# SpeedOfLightController.net
KiCad netlist of a schematic drawn in EAGLE
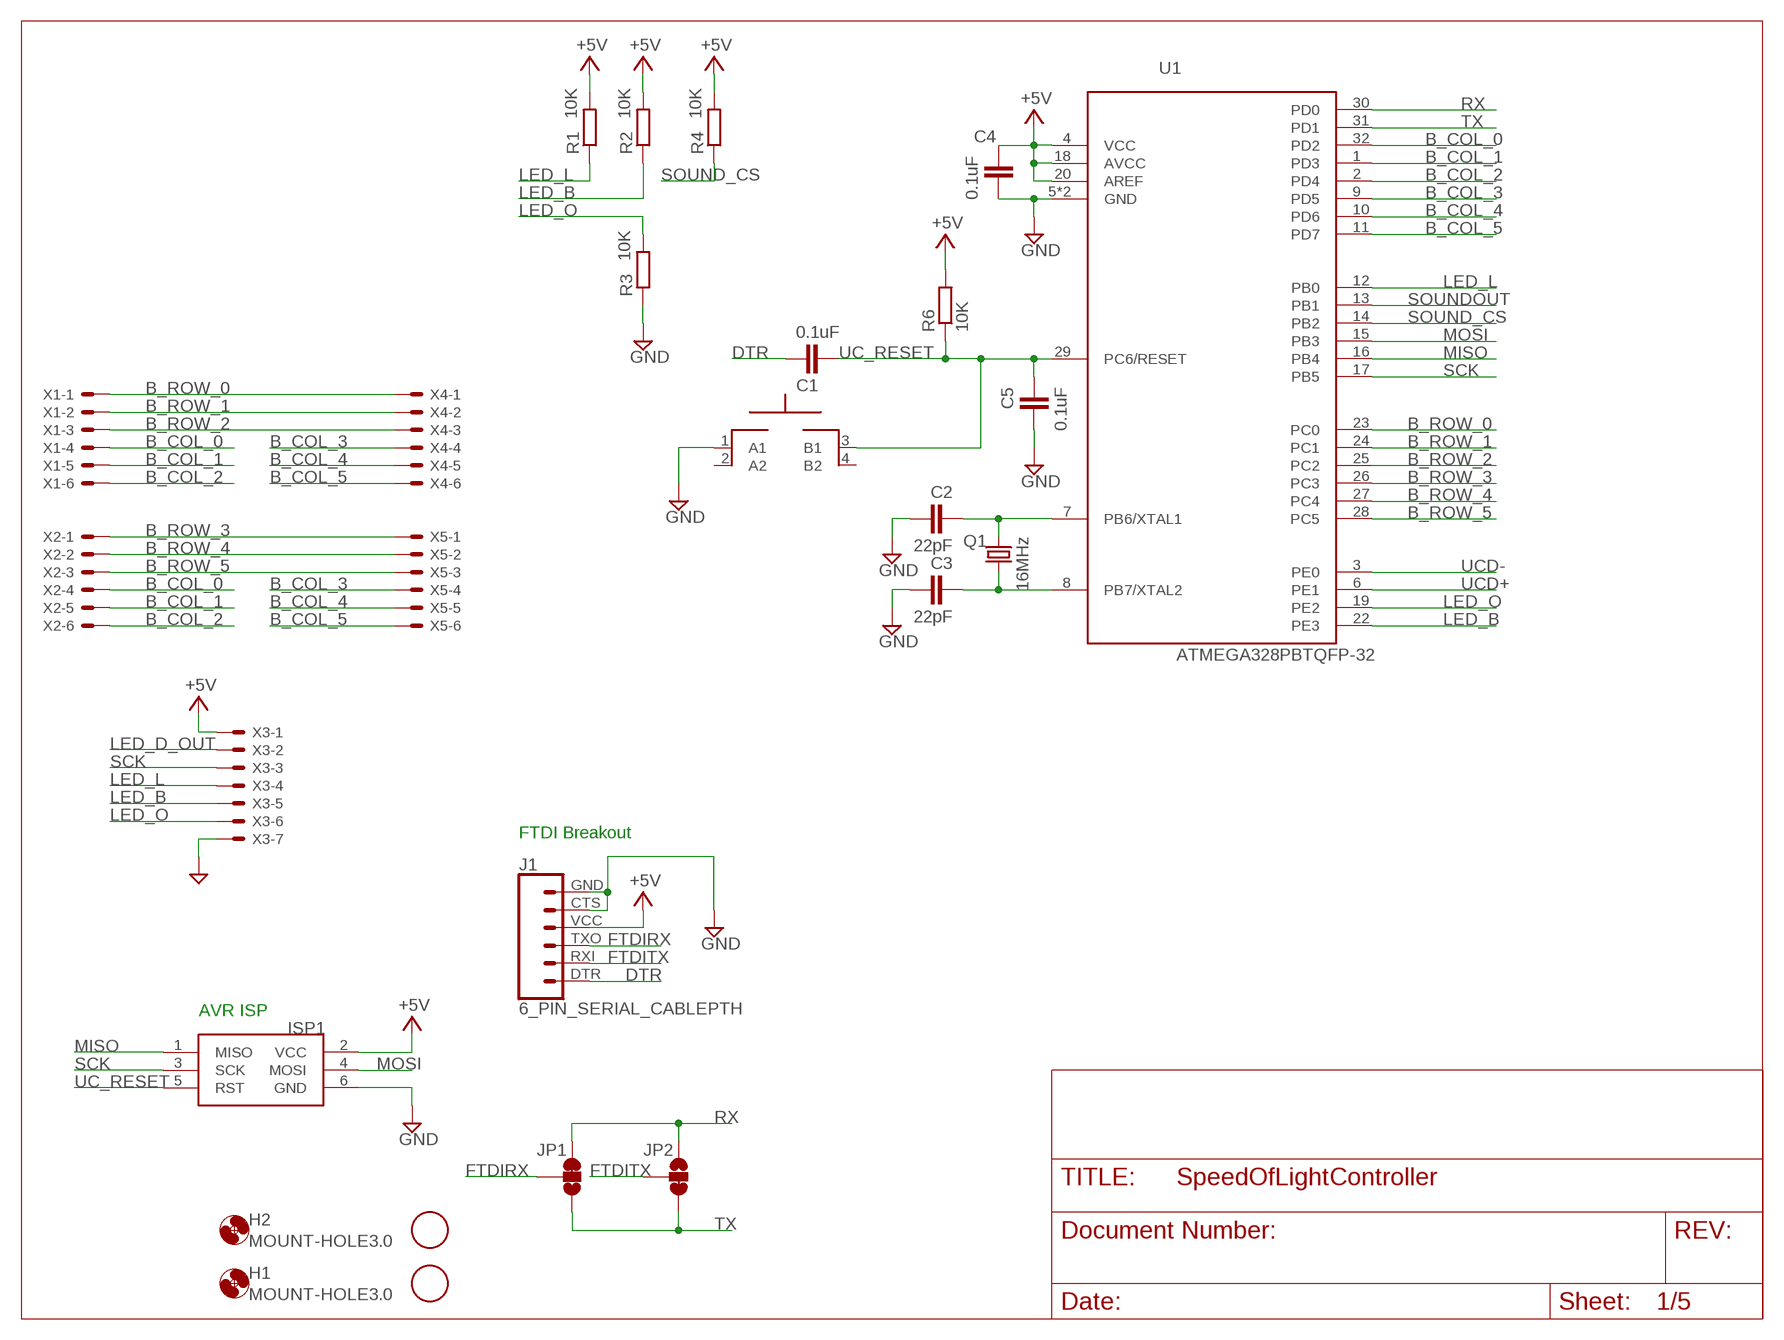
[diagram p0: schematic, sheet 1]
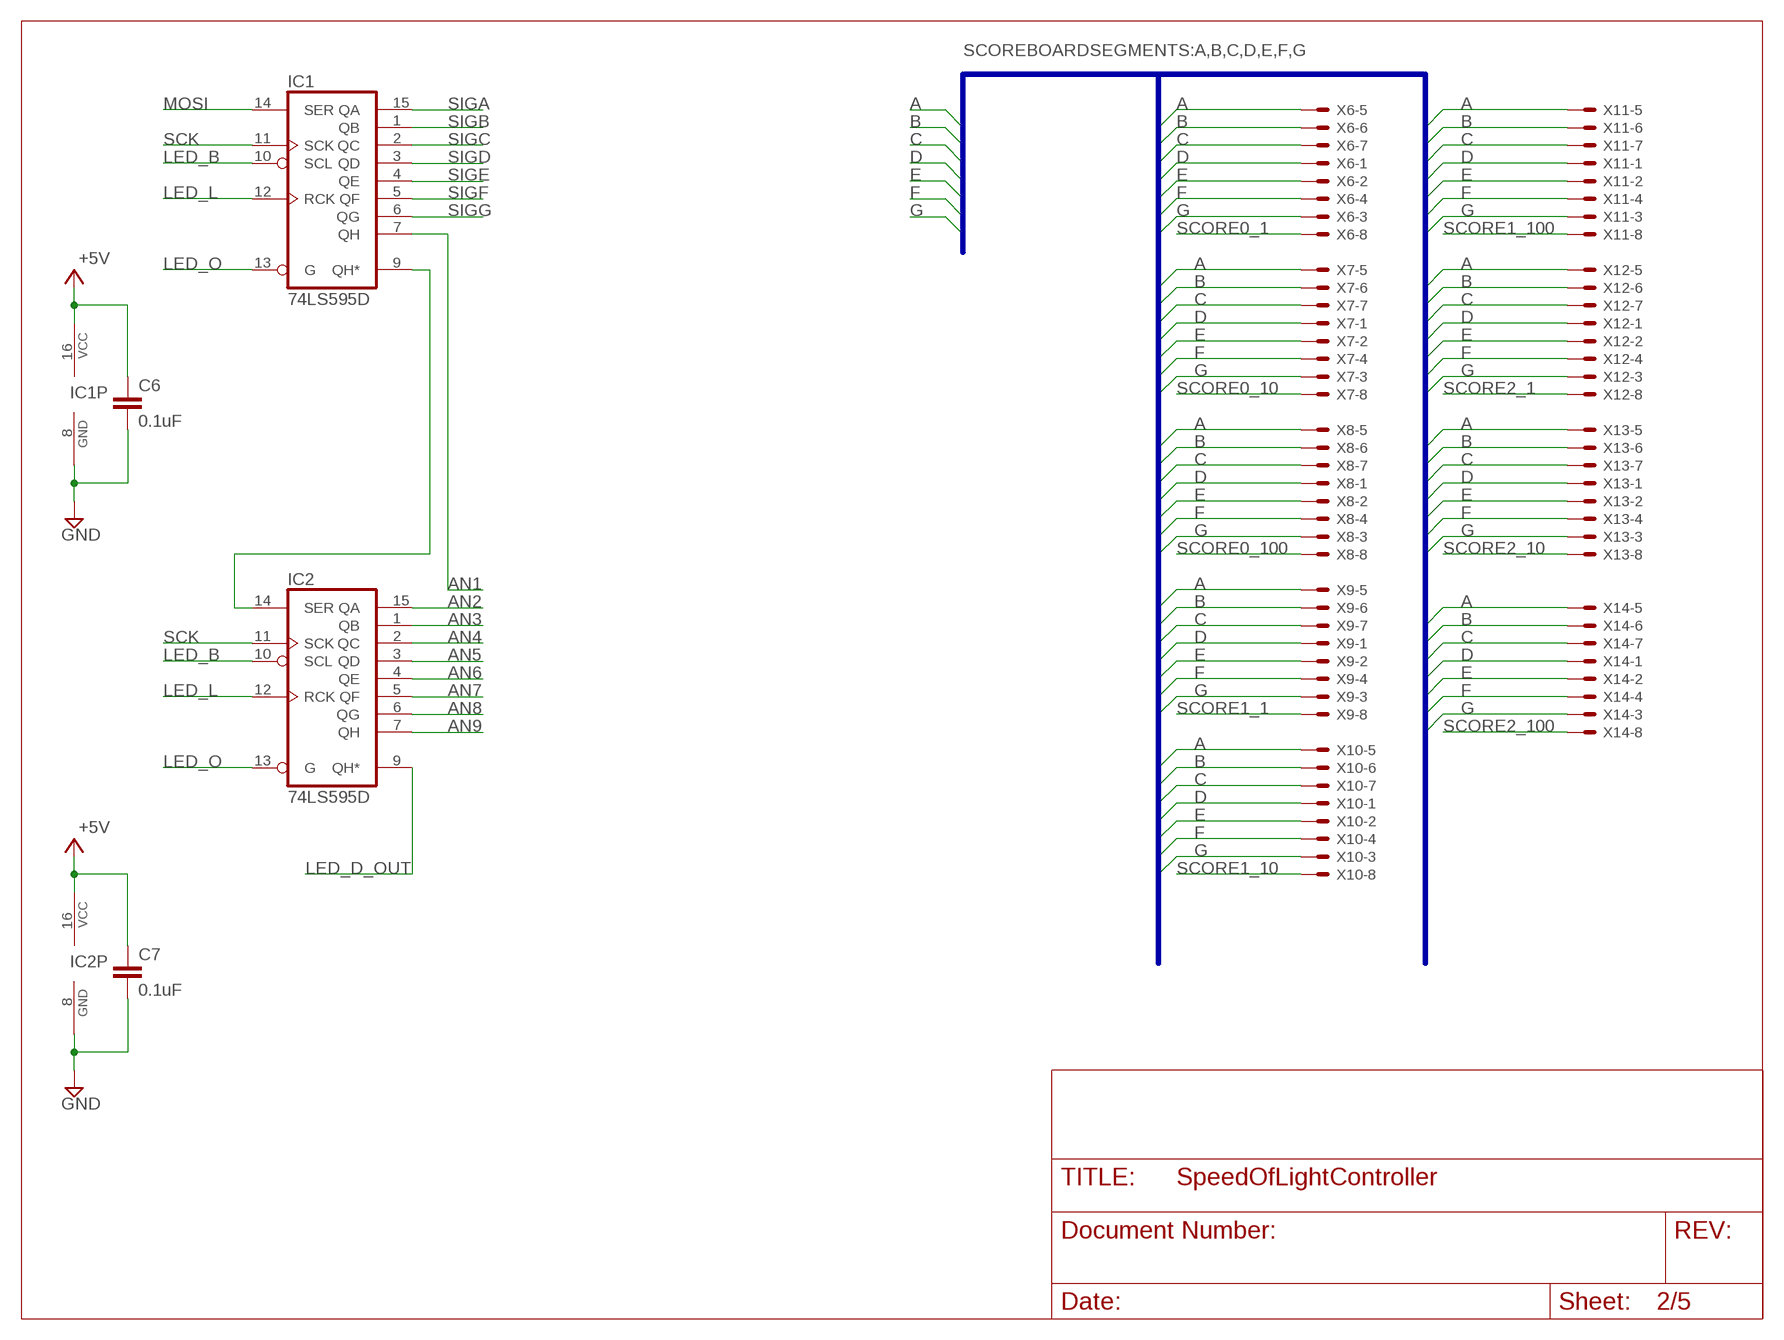
[diagram p1: schematic, sheet 2]
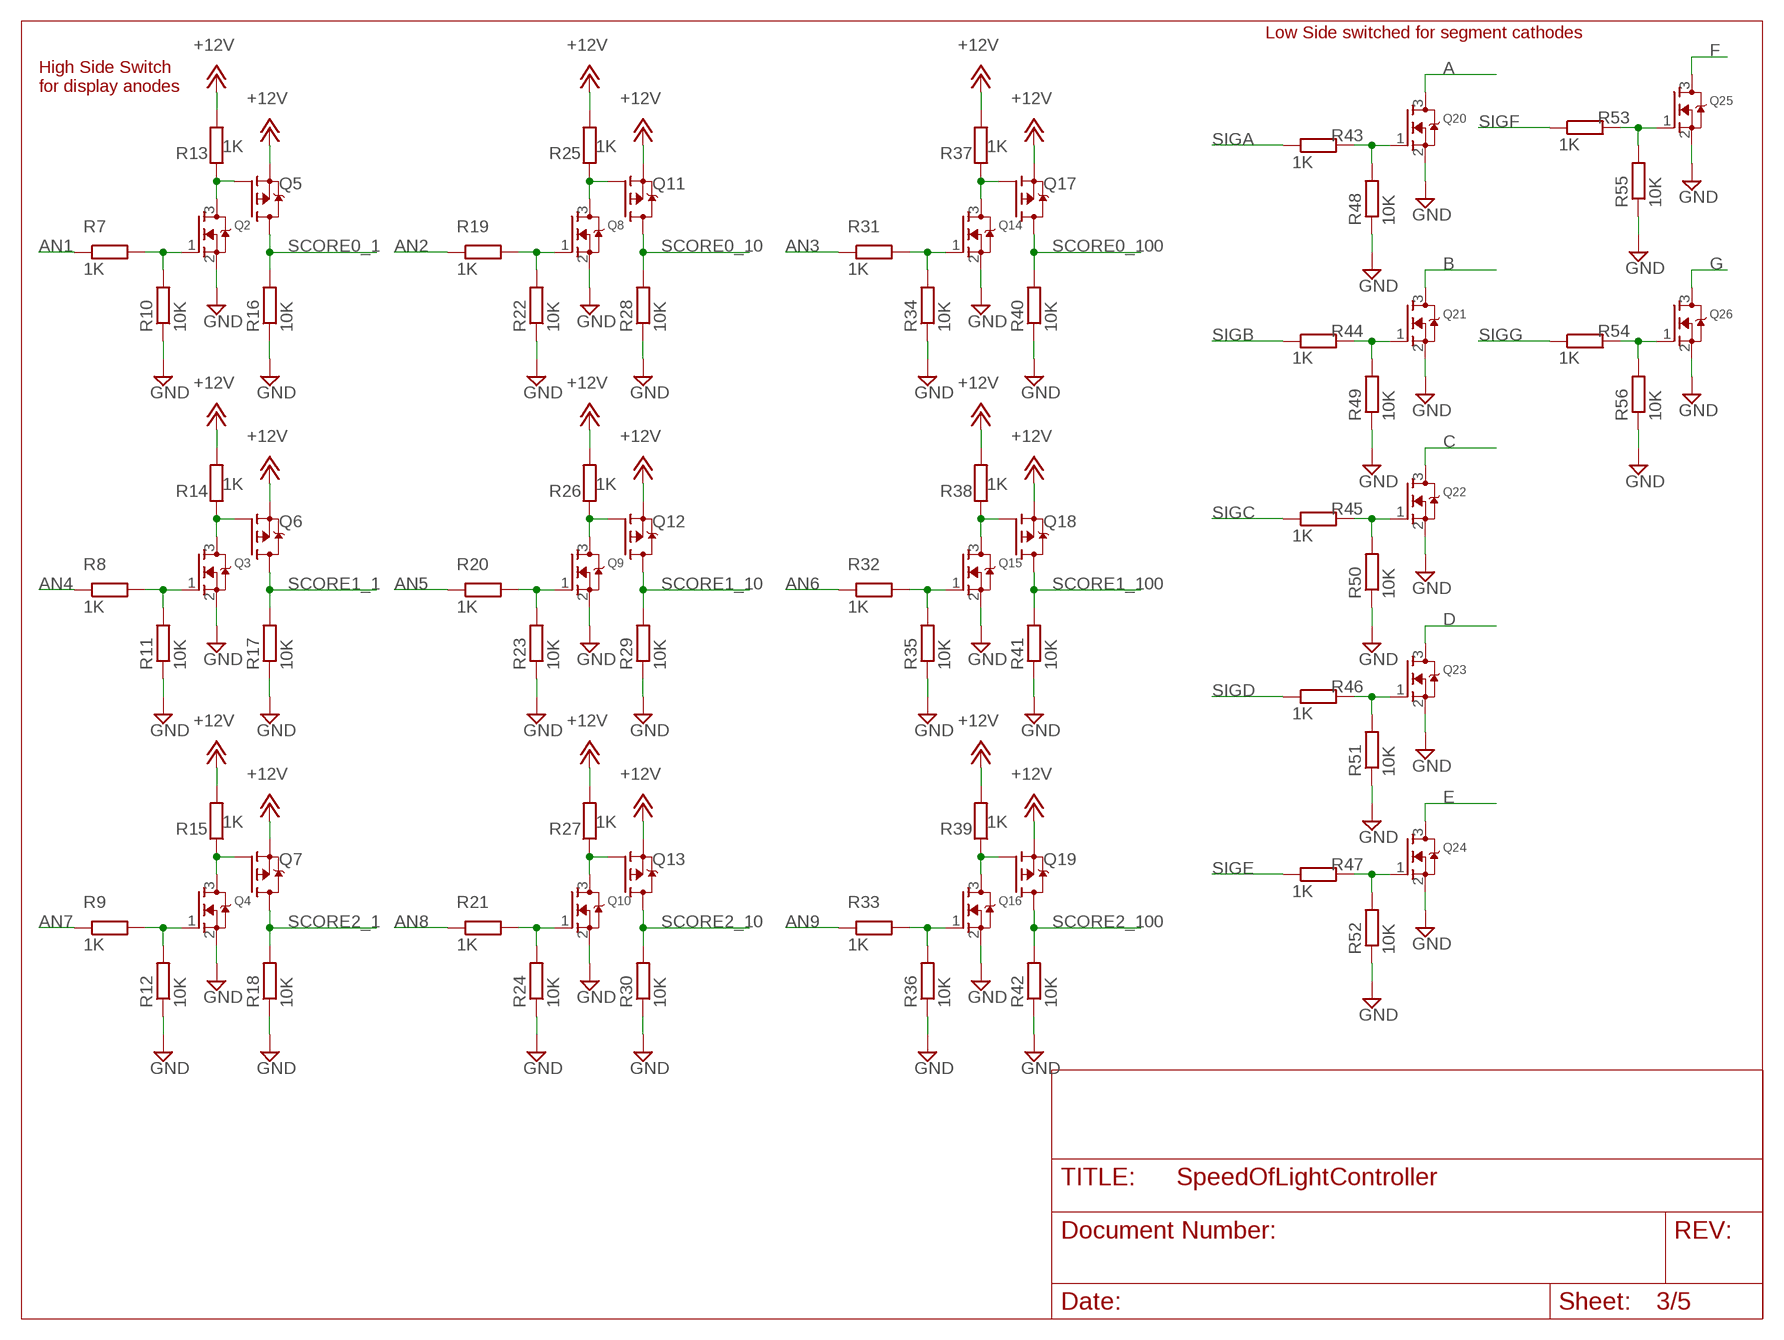
[diagram p2: schematic, sheet 3]
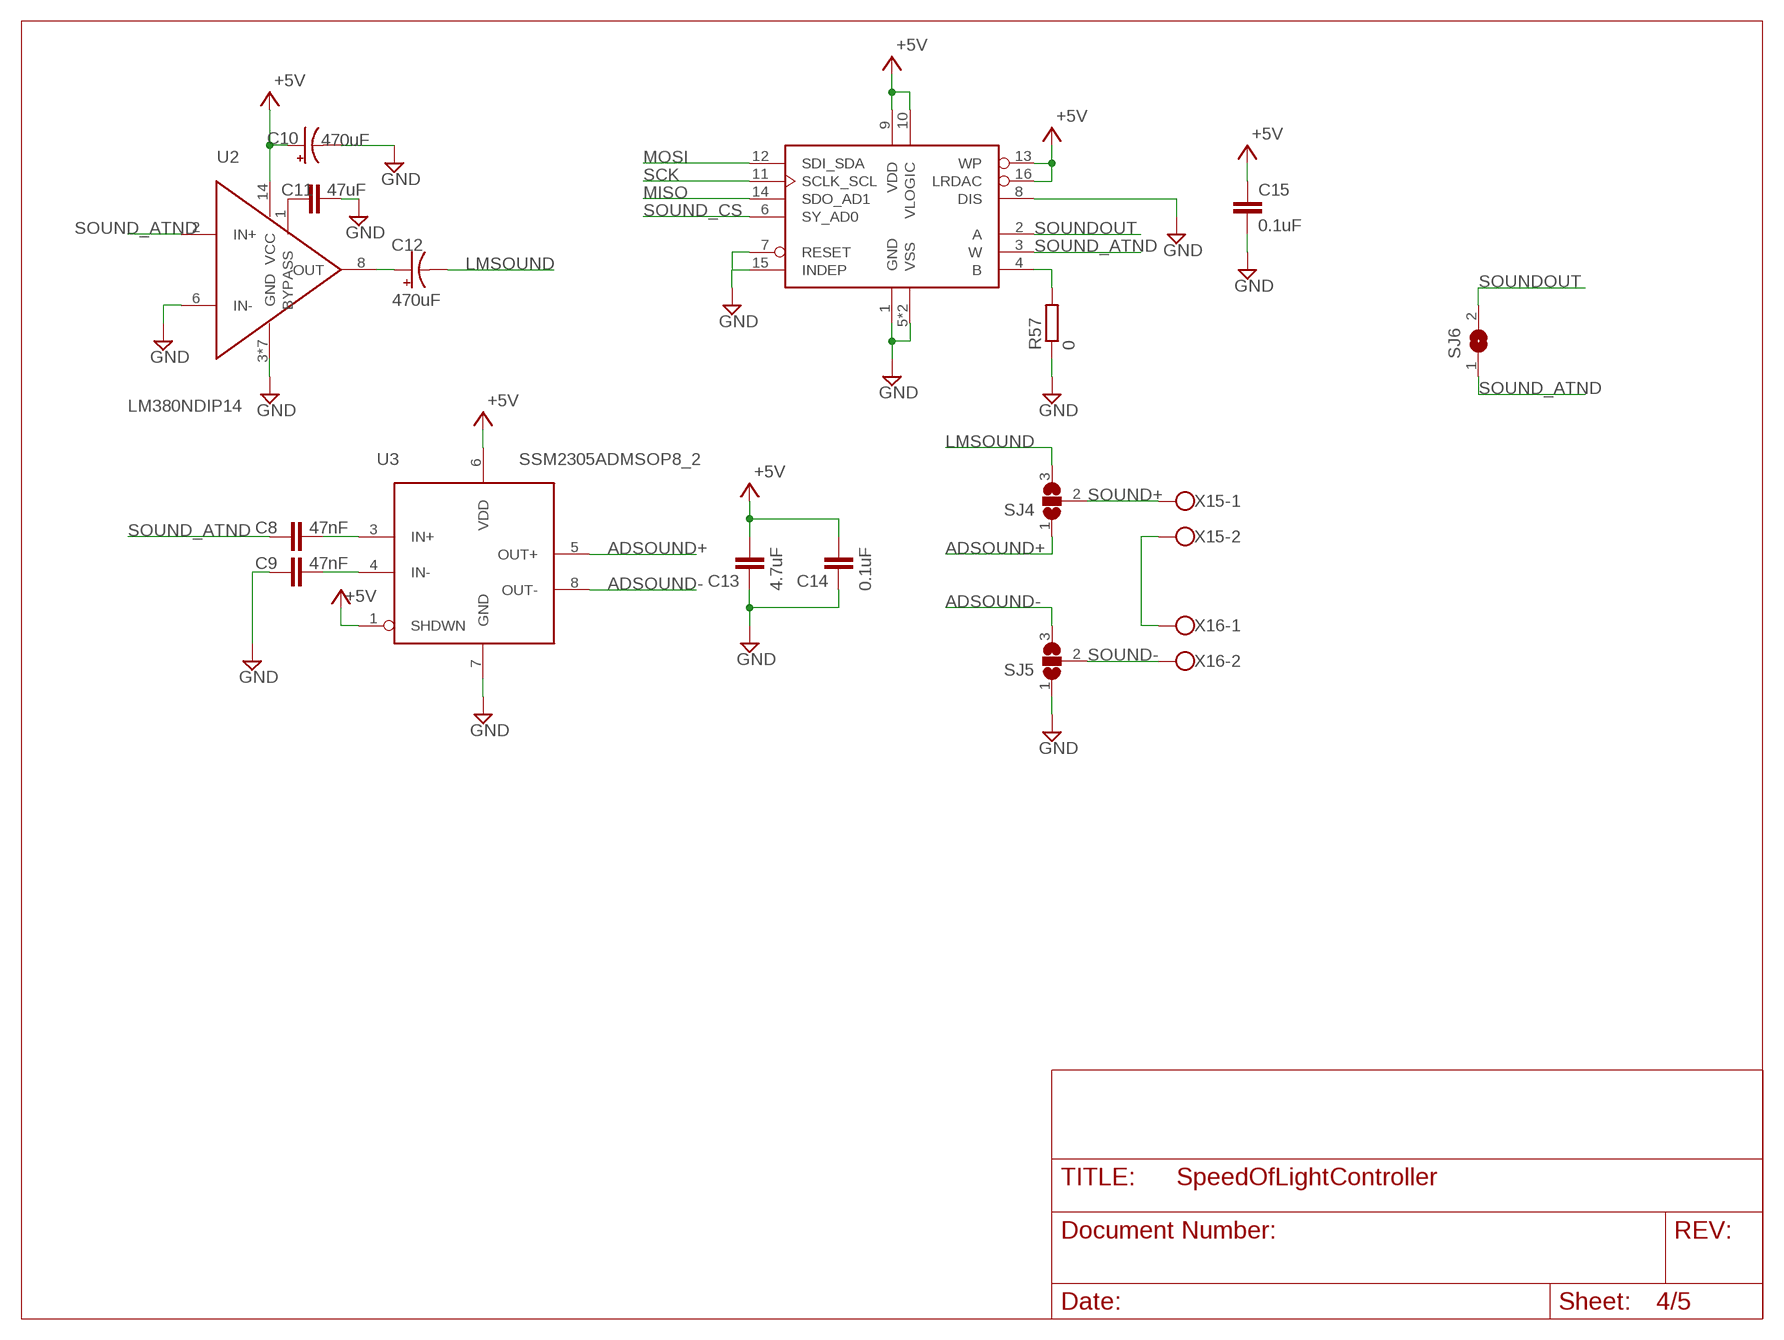
[diagram p3: schematic, sheet 4]
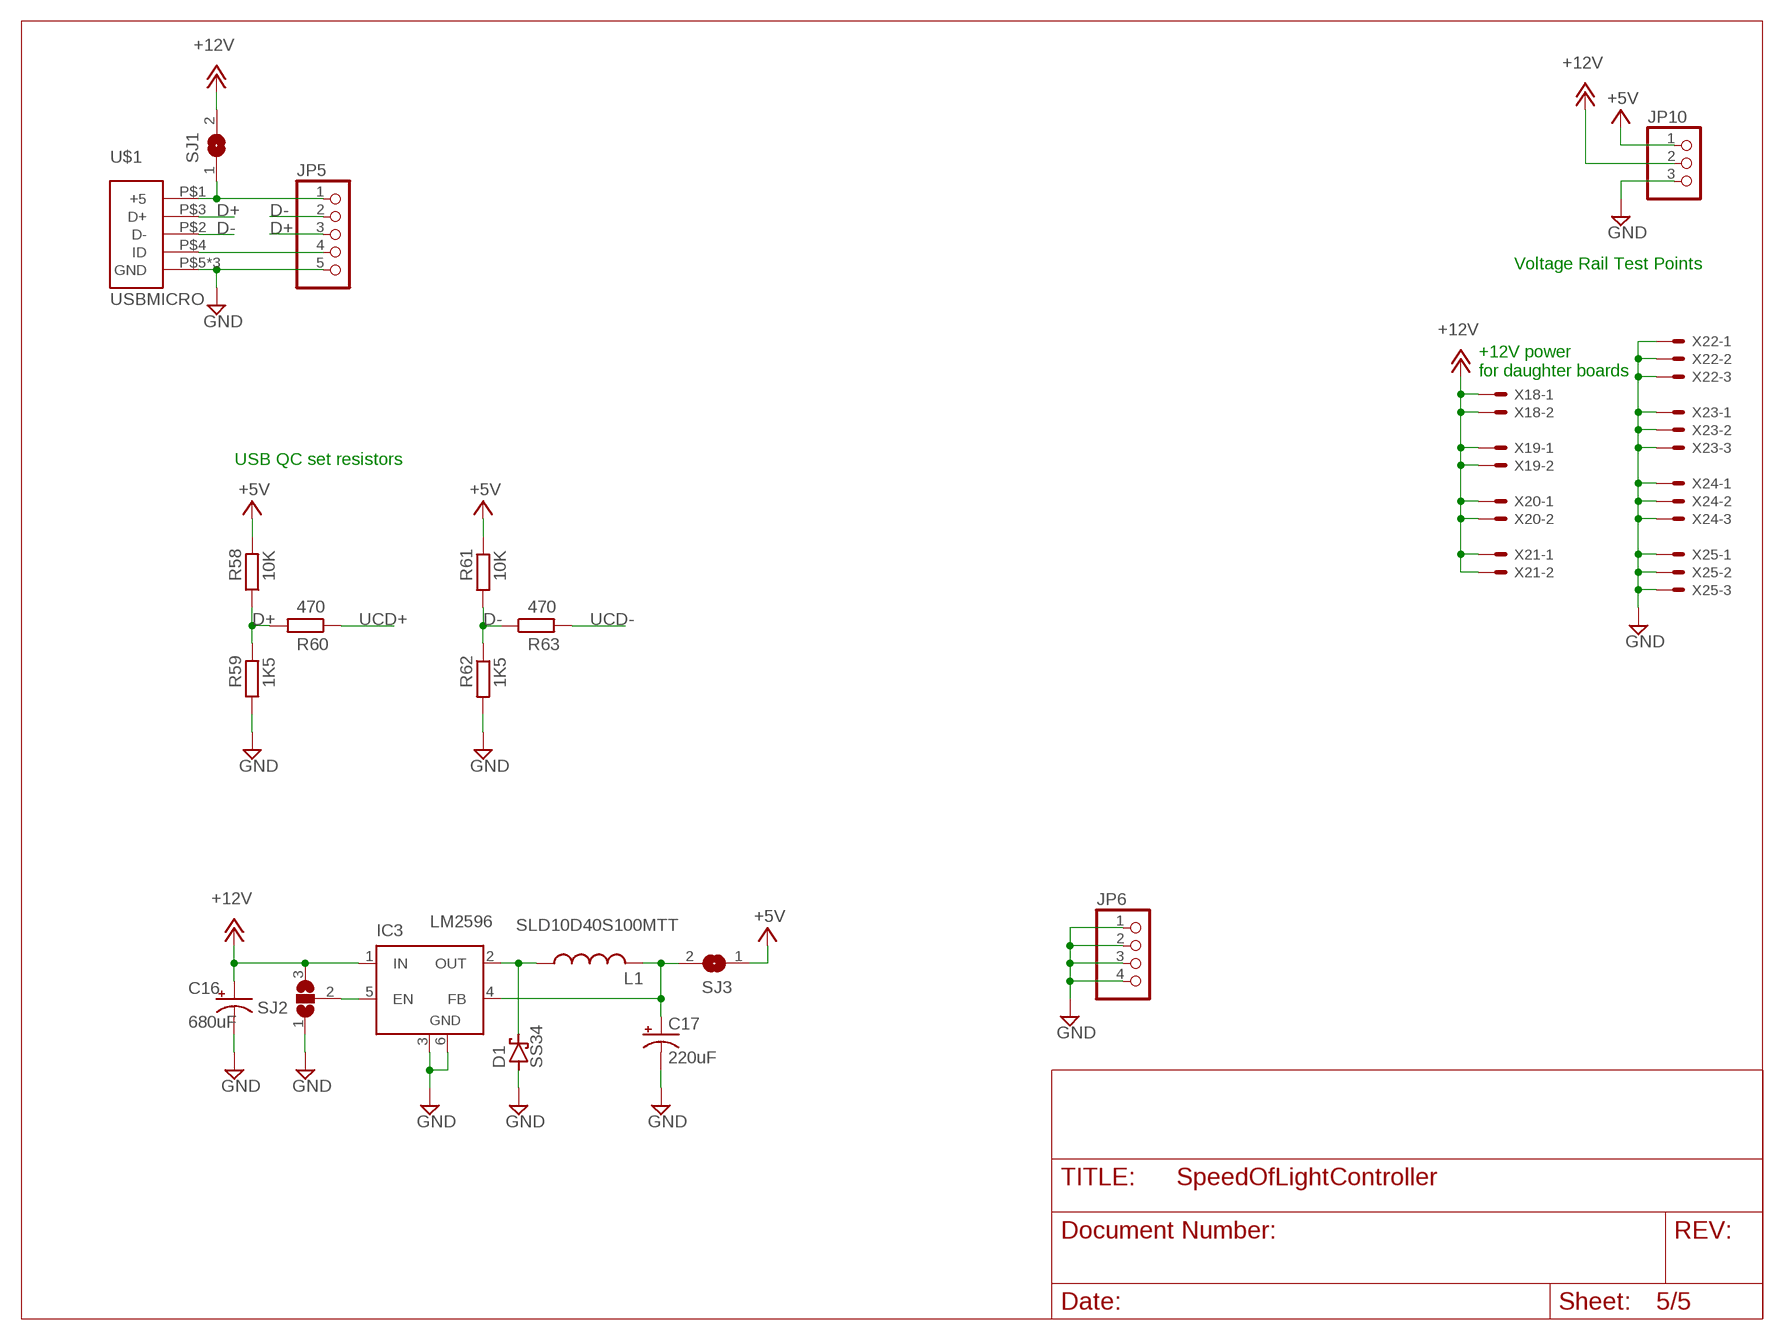
[diagram p4: schematic, sheet 5]

(export (version "E")
  (design (tool "Eeschema 10.0.6"))
  (components
    (comp (ref "Q2")
      (value "AO3414SOT23")
      (footprint "eagle-import:SOT95P240X110-3N")
      (libsource (lib "eagle-import") (part "AO3414SOT23"))
    )
    (comp (ref "Q3")
      (value "AO3414SOT23")
      (footprint "eagle-import:SOT95P240X110-3N")
      (libsource (lib "eagle-import") (part "AO3414SOT23"))
    )
    (comp (ref "Q4")
      (value "AO3414SOT23")
      (footprint "eagle-import:SOT95P240X110-3N")
      (libsource (lib "eagle-import") (part "AO3414SOT23"))
    )
    (comp (ref "Q5")
      (value "AO3415")
      (footprint "eagle-import:SOT95P240X110-3N")
      (libsource (lib "eagle-import") (part "AO3415"))
    )
    (comp (ref "Q6")
      (value "AO3415")
      (footprint "eagle-import:SOT95P240X110-3N")
      (libsource (lib "eagle-import") (part "AO3415"))
    )
    (comp (ref "Q7")
      (value "AO3415")
      (footprint "eagle-import:SOT95P240X110-3N")
      (libsource (lib "eagle-import") (part "AO3415"))
    )
    (comp (ref "Q8")
      (value "AO3414SOT23")
      (footprint "eagle-import:SOT95P240X110-3N")
      (libsource (lib "eagle-import") (part "AO3414SOT23"))
    )
    (comp (ref "Q9")
      (value "AO3414SOT23")
      (footprint "eagle-import:SOT95P240X110-3N")
      (libsource (lib "eagle-import") (part "AO3414SOT23"))
    )
    (comp (ref "Q10")
      (value "AO3414SOT23")
      (footprint "eagle-import:SOT95P240X110-3N")
      (libsource (lib "eagle-import") (part "AO3414SOT23"))
    )
    (comp (ref "Q11")
      (value "AO3415")
      (footprint "eagle-import:SOT95P240X110-3N")
      (libsource (lib "eagle-import") (part "AO3415"))
    )
    (comp (ref "Q12")
      (value "AO3415")
      (footprint "eagle-import:SOT95P240X110-3N")
      (libsource (lib "eagle-import") (part "AO3415"))
    )
    (comp (ref "Q13")
      (value "AO3415")
      (footprint "eagle-import:SOT95P240X110-3N")
      (libsource (lib "eagle-import") (part "AO3415"))
    )
    (comp (ref "Q14")
      (value "AO3414SOT23")
      (footprint "eagle-import:SOT95P240X110-3N")
      (libsource (lib "eagle-import") (part "AO3414SOT23"))
    )
    (comp (ref "Q15")
      (value "AO3414SOT23")
      (footprint "eagle-import:SOT95P240X110-3N")
      (libsource (lib "eagle-import") (part "AO3414SOT23"))
    )
    (comp (ref "Q16")
      (value "AO3414SOT23")
      (footprint "eagle-import:SOT95P240X110-3N")
      (libsource (lib "eagle-import") (part "AO3414SOT23"))
    )
    (comp (ref "Q17")
      (value "AO3415")
      (footprint "eagle-import:SOT95P240X110-3N")
      (libsource (lib "eagle-import") (part "AO3415"))
    )
    (comp (ref "Q18")
      (value "AO3415")
      (footprint "eagle-import:SOT95P240X110-3N")
      (libsource (lib "eagle-import") (part "AO3415"))
    )
    (comp (ref "Q19")
      (value "AO3415")
      (footprint "eagle-import:SOT95P240X110-3N")
      (libsource (lib "eagle-import") (part "AO3415"))
    )
    (comp (ref "Q20")
      (value "AO3414SOT23")
      (footprint "eagle-import:SOT95P240X110-3N")
      (libsource (lib "eagle-import") (part "AO3414SOT23"))
    )
    (comp (ref "Q21")
      (value "AO3414SOT23")
      (footprint "eagle-import:SOT95P240X110-3N")
      (libsource (lib "eagle-import") (part "AO3414SOT23"))
    )
    (comp (ref "Q22")
      (value "AO3414SOT23")
      (footprint "eagle-import:SOT95P240X110-3N")
      (libsource (lib "eagle-import") (part "AO3414SOT23"))
    )
    (comp (ref "Q23")
      (value "AO3414SOT23")
      (footprint "eagle-import:SOT95P240X110-3N")
      (libsource (lib "eagle-import") (part "AO3414SOT23"))
    )
    (comp (ref "Q24")
      (value "AO3414SOT23")
      (footprint "eagle-import:SOT95P240X110-3N")
      (libsource (lib "eagle-import") (part "AO3414SOT23"))
    )
    (comp (ref "Q25")
      (value "AO3414SOT23")
      (footprint "eagle-import:SOT95P240X110-3N")
      (libsource (lib "eagle-import") (part "AO3414SOT23"))
    )
    (comp (ref "Q26")
      (value "AO3414SOT23")
      (footprint "eagle-import:SOT95P240X110-3N")
      (libsource (lib "eagle-import") (part "AO3414SOT23"))
    )
    (comp (ref "R7")
      (value "1K")
      (footprint "eagle-import:R0805")
      (libsource (lib "eagle-import") (part "R-EU_R0805"))
    )
    (comp (ref "R8")
      (value "1K")
      (footprint "eagle-import:R0805")
      (libsource (lib "eagle-import") (part "R-EU_R0805"))
    )
    (comp (ref "R9")
      (value "1K")
      (footprint "eagle-import:R0805")
      (libsource (lib "eagle-import") (part "R-EU_R0805"))
    )
    (comp (ref "R10")
      (value "10K")
      (footprint "eagle-import:R0805")
      (libsource (lib "eagle-import") (part "R-EU_R0805"))
    )
    (comp (ref "R11")
      (value "10K")
      (footprint "eagle-import:R0805")
      (libsource (lib "eagle-import") (part "R-EU_R0805"))
    )
    (comp (ref "R12")
      (value "10K")
      (footprint "eagle-import:R0805")
      (libsource (lib "eagle-import") (part "R-EU_R0805"))
    )
    (comp (ref "R13")
      (value "1K")
      (footprint "eagle-import:R0805")
      (libsource (lib "eagle-import") (part "R-EU_R0805"))
    )
    (comp (ref "R14")
      (value "1K")
      (footprint "eagle-import:R0805")
      (libsource (lib "eagle-import") (part "R-EU_R0805"))
    )
    (comp (ref "R15")
      (value "1K")
      (footprint "eagle-import:R0805")
      (libsource (lib "eagle-import") (part "R-EU_R0805"))
    )
    (comp (ref "R16")
      (value "10K")
      (footprint "eagle-import:R0805")
      (libsource (lib "eagle-import") (part "R-EU_R0805"))
    )
    (comp (ref "R17")
      (value "10K")
      (footprint "eagle-import:R0805")
      (libsource (lib "eagle-import") (part "R-EU_R0805"))
    )
    (comp (ref "R18")
      (value "10K")
      (footprint "eagle-import:R0805")
      (libsource (lib "eagle-import") (part "R-EU_R0805"))
    )
    (comp (ref "R19")
      (value "1K")
      (footprint "eagle-import:R0805")
      (libsource (lib "eagle-import") (part "R-EU_R0805"))
    )
    (comp (ref "R20")
      (value "1K")
      (footprint "eagle-import:R0805")
      (libsource (lib "eagle-import") (part "R-EU_R0805"))
    )
    (comp (ref "R21")
      (value "1K")
      (footprint "eagle-import:R0805")
      (libsource (lib "eagle-import") (part "R-EU_R0805"))
    )
    (comp (ref "R22")
      (value "10K")
      (footprint "eagle-import:R0805")
      (libsource (lib "eagle-import") (part "R-EU_R0805"))
    )
    (comp (ref "R23")
      (value "10K")
      (footprint "eagle-import:R0805")
      (libsource (lib "eagle-import") (part "R-EU_R0805"))
    )
    (comp (ref "R24")
      (value "10K")
      (footprint "eagle-import:R0805")
      (libsource (lib "eagle-import") (part "R-EU_R0805"))
    )
    (comp (ref "R25")
      (value "1K")
      (footprint "eagle-import:R0805")
      (libsource (lib "eagle-import") (part "R-EU_R0805"))
    )
    (comp (ref "R26")
      (value "1K")
      (footprint "eagle-import:R0805")
      (libsource (lib "eagle-import") (part "R-EU_R0805"))
    )
    (comp (ref "R27")
      (value "1K")
      (footprint "eagle-import:R0805")
      (libsource (lib "eagle-import") (part "R-EU_R0805"))
    )
    (comp (ref "R28")
      (value "10K")
      (footprint "eagle-import:R0805")
      (libsource (lib "eagle-import") (part "R-EU_R0805"))
    )
    (comp (ref "R29")
      (value "10K")
      (footprint "eagle-import:R0805")
      (libsource (lib "eagle-import") (part "R-EU_R0805"))
    )
    (comp (ref "R30")
      (value "10K")
      (footprint "eagle-import:R0805")
      (libsource (lib "eagle-import") (part "R-EU_R0805"))
    )
    (comp (ref "R31")
      (value "1K")
      (footprint "eagle-import:R0805")
      (libsource (lib "eagle-import") (part "R-EU_R0805"))
    )
    (comp (ref "R32")
      (value "1K")
      (footprint "eagle-import:R0805")
      (libsource (lib "eagle-import") (part "R-EU_R0805"))
    )
    (comp (ref "R33")
      (value "1K")
      (footprint "eagle-import:R0805")
      (libsource (lib "eagle-import") (part "R-EU_R0805"))
    )
    (comp (ref "R34")
      (value "10K")
      (footprint "eagle-import:R0805")
      (libsource (lib "eagle-import") (part "R-EU_R0805"))
    )
    (comp (ref "R35")
      (value "10K")
      (footprint "eagle-import:R0805")
      (libsource (lib "eagle-import") (part "R-EU_R0805"))
    )
    (comp (ref "R36")
      (value "10K")
      (footprint "eagle-import:R0805")
      (libsource (lib "eagle-import") (part "R-EU_R0805"))
    )
    (comp (ref "R37")
      (value "1K")
      (footprint "eagle-import:R0805")
      (libsource (lib "eagle-import") (part "R-EU_R0805"))
    )
    (comp (ref "R38")
      (value "1K")
      (footprint "eagle-import:R0805")
      (libsource (lib "eagle-import") (part "R-EU_R0805"))
    )
    (comp (ref "R39")
      (value "1K")
      (footprint "eagle-import:R0805")
      (libsource (lib "eagle-import") (part "R-EU_R0805"))
    )
    (comp (ref "R40")
      (value "10K")
      (footprint "eagle-import:R0805")
      (libsource (lib "eagle-import") (part "R-EU_R0805"))
    )
    (comp (ref "R41")
      (value "10K")
      (footprint "eagle-import:R0805")
      (libsource (lib "eagle-import") (part "R-EU_R0805"))
    )
    (comp (ref "R42")
      (value "10K")
      (footprint "eagle-import:R0805")
      (libsource (lib "eagle-import") (part "R-EU_R0805"))
    )
    (comp (ref "R43")
      (value "1K")
      (footprint "eagle-import:R0805")
      (libsource (lib "eagle-import") (part "R-EU_R0805"))
    )
    (comp (ref "R44")
      (value "1K")
      (footprint "eagle-import:R0805")
      (libsource (lib "eagle-import") (part "R-EU_R0805"))
    )
    (comp (ref "R45")
      (value "1K")
      (footprint "eagle-import:R0805")
      (libsource (lib "eagle-import") (part "R-EU_R0805"))
    )
    (comp (ref "R46")
      (value "1K")
      (footprint "eagle-import:R0805")
      (libsource (lib "eagle-import") (part "R-EU_R0805"))
    )
    (comp (ref "R47")
      (value "1K")
      (footprint "eagle-import:R0805")
      (libsource (lib "eagle-import") (part "R-EU_R0805"))
    )
    (comp (ref "R48")
      (value "10K")
      (footprint "eagle-import:R0805")
      (libsource (lib "eagle-import") (part "R-EU_R0805"))
    )
    (comp (ref "R49")
      (value "10K")
      (footprint "eagle-import:R0805")
      (libsource (lib "eagle-import") (part "R-EU_R0805"))
    )
    (comp (ref "R50")
      (value "10K")
      (footprint "eagle-import:R0805")
      (libsource (lib "eagle-import") (part "R-EU_R0805"))
    )
    (comp (ref "R51")
      (value "10K")
      (footprint "eagle-import:R0805")
      (libsource (lib "eagle-import") (part "R-EU_R0805"))
    )
    (comp (ref "R52")
      (value "10K")
      (footprint "eagle-import:R0805")
      (libsource (lib "eagle-import") (part "R-EU_R0805"))
    )
    (comp (ref "R53")
      (value "1K")
      (footprint "eagle-import:R0805")
      (libsource (lib "eagle-import") (part "R-EU_R0805"))
    )
    (comp (ref "R54")
      (value "1K")
      (footprint "eagle-import:R0805")
      (libsource (lib "eagle-import") (part "R-EU_R0805"))
    )
    (comp (ref "R55")
      (value "10K")
      (footprint "eagle-import:R0805")
      (libsource (lib "eagle-import") (part "R-EU_R0805"))
    )
    (comp (ref "R56")
      (value "10K")
      (footprint "eagle-import:R0805")
      (libsource (lib "eagle-import") (part "R-EU_R0805"))
    )
    (comp (ref "C6")
      (value "0.1uF")
      (footprint "eagle-import:C0805")
      (libsource (lib "eagle-import") (part "C-EUC0805"))
    )
    (comp (ref "C7")
      (value "0.1uF")
      (footprint "eagle-import:C0805")
      (libsource (lib "eagle-import") (part "C-EUC0805"))
    )
    (comp (ref "IC1")
      (value "74LS595D")
      (footprint "eagle-import:SO16")
      (libsource (lib "eagle-import") (part "74595DLS"))
    )
    (comp (ref "IC2")
      (value "74LS595D")
      (footprint "eagle-import:SO16")
      (libsource (lib "eagle-import") (part "74595DLS"))
    )
    (comp (ref "X6")
      (value "JST-XH-08-PIN-LONG-PAD")
      (footprint "eagle-import:JST-XH-08-PACKAGE-LONG-PAD")
      (libsource (lib "eagle-import") (part "JST-XH-08-PIN-LONG-PAD"))
    )
    (comp (ref "X7")
      (value "JST-XH-08-PIN-LONG-PAD")
      (footprint "eagle-import:JST-XH-08-PACKAGE-LONG-PAD")
      (libsource (lib "eagle-import") (part "JST-XH-08-PIN-LONG-PAD"))
    )
    (comp (ref "X8")
      (value "JST-XH-08-PIN-LONG-PAD")
      (footprint "eagle-import:JST-XH-08-PACKAGE-LONG-PAD")
      (libsource (lib "eagle-import") (part "JST-XH-08-PIN-LONG-PAD"))
    )
    (comp (ref "X9")
      (value "JST-XH-08-PIN-LONG-PAD")
      (footprint "eagle-import:JST-XH-08-PACKAGE-LONG-PAD")
      (libsource (lib "eagle-import") (part "JST-XH-08-PIN-LONG-PAD"))
    )
    (comp (ref "X10")
      (value "JST-XH-08-PIN-LONG-PAD")
      (footprint "eagle-import:JST-XH-08-PACKAGE-LONG-PAD")
      (libsource (lib "eagle-import") (part "JST-XH-08-PIN-LONG-PAD"))
    )
    (comp (ref "X11")
      (value "JST-XH-08-PIN-LONG-PAD")
      (footprint "eagle-import:JST-XH-08-PACKAGE-LONG-PAD")
      (libsource (lib "eagle-import") (part "JST-XH-08-PIN-LONG-PAD"))
    )
    (comp (ref "X12")
      (value "JST-XH-08-PIN-LONG-PAD")
      (footprint "eagle-import:JST-XH-08-PACKAGE-LONG-PAD")
      (libsource (lib "eagle-import") (part "JST-XH-08-PIN-LONG-PAD"))
    )
    (comp (ref "X13")
      (value "JST-XH-08-PIN-LONG-PAD")
      (footprint "eagle-import:JST-XH-08-PACKAGE-LONG-PAD")
      (libsource (lib "eagle-import") (part "JST-XH-08-PIN-LONG-PAD"))
    )
    (comp (ref "X14")
      (value "JST-XH-08-PIN-LONG-PAD")
      (footprint "eagle-import:JST-XH-08-PACKAGE-LONG-PAD")
      (libsource (lib "eagle-import") (part "JST-XH-08-PIN-LONG-PAD"))
    )
    (comp (ref "C8")
      (value "47nF")
      (footprint "eagle-import:C0805")
      (libsource (lib "eagle-import") (part "C-EUC0805"))
    )
    (comp (ref "C9")
      (value "47nF")
      (footprint "eagle-import:C0805")
      (libsource (lib "eagle-import") (part "C-EUC0805"))
    )
    (comp (ref "C10")
      (value "470uF")
      (footprint "eagle-import:140CLH-0810")
      (libsource (lib "eagle-import") (part "CPOL-US140CLH-0810"))
    )
    (comp (ref "C11")
      (value "47uF")
      (footprint "eagle-import:C0805")
      (libsource (lib "eagle-import") (part "C-EUC0805"))
    )
    (comp (ref "C12")
      (value "470uF")
      (footprint "eagle-import:140CLH-0810")
      (libsource (lib "eagle-import") (part "CPOL-US140CLH-0810"))
    )
    (comp (ref "C13")
      (value "4.7uF")
      (footprint "eagle-import:C0805")
      (libsource (lib "eagle-import") (part "C-EUC0805"))
    )
    (comp (ref "C14")
      (value "0.1uF")
      (footprint "eagle-import:C0805")
      (libsource (lib "eagle-import") (part "C-EUC0805"))
    )
    (comp (ref "C15")
      (value "0.1uF")
      (footprint "eagle-import:C0805")
      (libsource (lib "eagle-import") (part "C-EUC0805"))
    )
    (comp (ref "R57")
      (value "0")
      (footprint "eagle-import:R0805W")
      (libsource (lib "eagle-import") (part "R-EU_R0805W"))
    )
    (comp (ref "SJ4")
      (value "SJ2W")
      (footprint "eagle-import:SJ_2")
      (libsource (lib "eagle-import") (part "SJ2W"))
    )
    (comp (ref "SJ5")
      (value "SJ2W")
      (footprint "eagle-import:SJ_2")
      (libsource (lib "eagle-import") (part "SJ2W"))
    )
    (comp (ref "SJ6") (value "SJ") (footprint "eagle-import:SJ") (libsource (lib "eagle-import") (part "SJ")))
    (comp (ref "U2")
      (value "LM380NDIP14")
      (footprint "eagle-import:DIP762W53P254L1969H508Q14B")
      (libsource (lib "eagle-import") (part "LM380NDIP14"))
    )
    (comp (ref "U3")
      (value "SSM2305ADMSOP8_2")
      (footprint "eagle-import:SOP65P490X95-8N")
      (libsource (lib "eagle-import") (part "SSM2305ADMSOP8_2"))
    )
    (comp (ref "U4")
      (value "AD5141ADLFCSP3")
      (footprint "eagle-import:QFN50P300X300X80-17T160N")
      (libsource (lib "eagle-import") (part "AD5141ADLFCSP3"))
    )
    (comp (ref "X15")
      (value "1X02_5MM_SCREW")
      (footprint "eagle-import:W237-102")
      (fields (field (name "MPN") "237-102"))
      (libsource (lib "eagle-import") (part "1X02_5MM_SCREW"))
    )
    (comp (ref "X16")
      (value "1X02_5MM_SCREW")
      (footprint "eagle-import:W237-102")
      (fields (field (name "MPN") "237-102"))
      (libsource (lib "eagle-import") (part "1X02_5MM_SCREW"))
    )
    (comp (ref "C16")
      (value "680uF")
      (footprint "eagle-import:140CLH-0810")
      (libsource (lib "eagle-import") (part "CPOL-US140CLH-0810"))
    )
    (comp (ref "C17")
      (value "220uF")
      (footprint "eagle-import:140CLH-0810")
      (libsource (lib "eagle-import") (part "CPOL-US140CLH-0810"))
    )
    (comp (ref "D1")
      (value "SS34")
      (footprint "eagle-import:SMA")
      (libsource (lib "eagle-import") (part "SS34"))
    )
    (comp (ref "IC3")
      (value "LM2596S")
      (footprint "eagle-import:TO263-5")
      (libsource (lib "eagle-import") (part "LM2596S"))
    )
    (comp (ref "JP5")
      (value "PINHD-1X5")
      (footprint "eagle-import:1X05")
      (libsource (lib "eagle-import") (part "PINHD-1X5"))
    )
    (comp (ref "JP6")
      (value "PINHD-1X4")
      (footprint "eagle-import:1X04")
      (libsource (lib "eagle-import") (part "PINHD-1X4"))
    )
    (comp (ref "JP10")
      (value "PINHD-1X3")
      (footprint "eagle-import:1X03")
      (libsource (lib "eagle-import") (part "PINHD-1X3"))
    )
    (comp (ref "L1")
      (value "SLD10D40S100MTT")
      (footprint "eagle-import:SMD10.5X10.3")
      (libsource (lib "eagle-import") (part "SLD10D40S100MTT"))
    )
    (comp (ref "R58")
      (value "10K")
      (footprint "eagle-import:R0805")
      (libsource (lib "eagle-import") (part "R-EU_R0805"))
    )
    (comp (ref "R59")
      (value "1K5")
      (footprint "eagle-import:R0805")
      (libsource (lib "eagle-import") (part "R-EU_R0805"))
    )
    (comp (ref "R60")
      (value "470")
      (footprint "eagle-import:R0805")
      (libsource (lib "eagle-import") (part "R-EU_R0805"))
    )
    (comp (ref "R61")
      (value "10K")
      (footprint "eagle-import:R0805")
      (libsource (lib "eagle-import") (part "R-EU_R0805"))
    )
    (comp (ref "R62")
      (value "1K5")
      (footprint "eagle-import:R0805")
      (libsource (lib "eagle-import") (part "R-EU_R0805"))
    )
    (comp (ref "R63")
      (value "470")
      (footprint "eagle-import:R0805")
      (libsource (lib "eagle-import") (part "R-EU_R0805"))
    )
    (comp (ref "SJ1") (value "SJ") (footprint "eagle-import:SJ") (libsource (lib "eagle-import") (part "SJ")))
    (comp (ref "SJ2")
      (value "SJ2WW")
      (footprint "eagle-import:SJ_2W")
      (libsource (lib "eagle-import") (part "SJ2WW"))
    )
    (comp (ref "SJ3") (value "SJ") (footprint "eagle-import:SJ") (libsource (lib "eagle-import") (part "SJ")))
    (comp (ref "U$1")
      (value "USBMICRO")
      (footprint "eagle-import:USBMICRO")
      (libsource (lib "eagle-import") (part "USBMICRO"))
    )
    (comp (ref "X18")
      (value "JST-XH-02-PIN-LONG-PAD")
      (footprint "eagle-import:JST-XH-02-PACKAGE-LONG-PAD")
      (libsource (lib "eagle-import") (part "JST-XH-02-PIN-LONG-PAD"))
    )
    (comp (ref "X19")
      (value "JST-XH-02-PIN-LONG-PAD")
      (footprint "eagle-import:JST-XH-02-PACKAGE-LONG-PAD")
      (libsource (lib "eagle-import") (part "JST-XH-02-PIN-LONG-PAD"))
    )
    (comp (ref "X20")
      (value "JST-XH-02-PIN-LONG-PAD")
      (footprint "eagle-import:JST-XH-02-PACKAGE-LONG-PAD")
      (libsource (lib "eagle-import") (part "JST-XH-02-PIN-LONG-PAD"))
    )
    (comp (ref "X21")
      (value "JST-XH-02-PIN-LONG-PAD")
      (footprint "eagle-import:JST-XH-02-PACKAGE-LONG-PAD")
      (libsource (lib "eagle-import") (part "JST-XH-02-PIN-LONG-PAD"))
    )
    (comp (ref "X22")
      (value "JST-XH-03-PIN-LONG-PAD")
      (footprint "eagle-import:JST-XH-03-PACKAGE-LONG-PAD")
      (libsource (lib "eagle-import") (part "JST-XH-03-PIN-LONG-PAD"))
    )
    (comp (ref "X23")
      (value "JST-XH-03-PIN-LONG-PAD")
      (footprint "eagle-import:JST-XH-03-PACKAGE-LONG-PAD")
      (libsource (lib "eagle-import") (part "JST-XH-03-PIN-LONG-PAD"))
    )
    (comp (ref "X24")
      (value "JST-XH-03-PIN-LONG-PAD")
      (footprint "eagle-import:JST-XH-03-PACKAGE-LONG-PAD")
      (libsource (lib "eagle-import") (part "JST-XH-03-PIN-LONG-PAD"))
    )
    (comp (ref "X25")
      (value "JST-XH-03-PIN-LONG-PAD")
      (footprint "eagle-import:JST-XH-03-PACKAGE-LONG-PAD")
      (libsource (lib "eagle-import") (part "JST-XH-03-PIN-LONG-PAD"))
    )
    (comp (ref "AF1")
      (value "FIDUCIAL")
      (footprint "eagle-import:FIDUCIAL_1MM")
      (libsource (lib "eagle-import") (part "FIDUCIAL"))
    )
    (comp (ref "AF2")
      (value "FIDUCIAL")
      (footprint "eagle-import:FIDUCIAL_1MM")
      (libsource (lib "eagle-import") (part "FIDUCIAL"))
    )
    (comp (ref "C1")
      (value "0.1uF")
      (footprint "eagle-import:C0805")
      (libsource (lib "eagle-import") (part "C-EUC0805"))
    )
    (comp (ref "C2")
      (value "22pF")
      (footprint "eagle-import:C0805")
      (libsource (lib "eagle-import") (part "C-EUC0805"))
    )
    (comp (ref "C3")
      (value "22pF")
      (footprint "eagle-import:C0805")
      (libsource (lib "eagle-import") (part "C-EUC0805"))
    )
    (comp (ref "C4")
      (value "0.1uF")
      (footprint "eagle-import:C0805")
      (libsource (lib "eagle-import") (part "C-EUC0805"))
    )
    (comp (ref "C5")
      (value "0.1uF")
      (footprint "eagle-import:C0805")
      (libsource (lib "eagle-import") (part "C-EUC0805"))
    )
    (comp (ref "H1")
      (value "MOUNT-HOLE3.0")
      (footprint "eagle-import:3,0")
      (libsource (lib "eagle-import") (part "MOUNT-HOLE3.0"))
    )
    (comp (ref "H2")
      (value "MOUNT-HOLE3.0")
      (footprint "eagle-import:3,0")
      (libsource (lib "eagle-import") (part "MOUNT-HOLE3.0"))
    )
    (comp (ref "ISP1")
      (value "AVRISP-6")
      (footprint "eagle-import:AVRISP")
      (libsource (lib "eagle-import") (part "AVRISP-6"))
    )
    (comp (ref "J1")
      (value "6_PIN_SERIAL_CABLEPTH")
      (footprint "eagle-import:FTDI_BASIC")
      (libsource (lib "eagle-import") (part "6_PIN_SERIAL_CABLEPTH"))
    )
    (comp (ref "JP1")
      (value "JUMPER-SMT_3_1-NC_TRACE_SILK")
      (footprint "eagle-import:SMT-JUMPER_3_1-NC_TRACE_SILK")
      (libsource (lib "eagle-import") (part "JUMPER-SMT_3_1-NC_TRACE_SILK"))
    )
    (comp (ref "JP2")
      (value "JUMPER-SMT_3_1-NC_TRACE_SILK")
      (footprint "eagle-import:SMT-JUMPER_3_1-NC_TRACE_SILK")
      (libsource (lib "eagle-import") (part "JUMPER-SMT_3_1-NC_TRACE_SILK"))
    )
    (comp (ref "Q1")
      (value "16MHz")
      (footprint "eagle-import:HC49UP")
      (libsource (lib "eagle-import") (part "CRYSTALHC49UP"))
    )
    (comp (ref "R1")
      (value "10K")
      (footprint "eagle-import:R0805")
      (libsource (lib "eagle-import") (part "R-EU_R0805"))
    )
    (comp (ref "R2")
      (value "10K")
      (footprint "eagle-import:R0805")
      (libsource (lib "eagle-import") (part "R-EU_R0805"))
    )
    (comp (ref "R3")
      (value "10K")
      (footprint "eagle-import:R0805")
      (libsource (lib "eagle-import") (part "R-EU_R0805"))
    )
    (comp (ref "R4")
      (value "10K")
      (footprint "eagle-import:R0805")
      (libsource (lib "eagle-import") (part "R-EU_R0805"))
    )
    (comp (ref "R6")
      (value "10K")
      (footprint "eagle-import:R0805")
      (libsource (lib "eagle-import") (part "R-EU_R0805"))
    )
    (comp (ref "RESET")
      (value "MOMENTARYBUTTON")
      (footprint "eagle-import:SPST_NO_SMD")
      (libsource (lib "eagle-import") (part "MOMENTARYBUTTON"))
    )
    (comp (ref "U1")
      (value "ATMEGA328PBTQFP-32")
      (footprint "eagle-import:QFP80P900X900X120-32N")
      (libsource (lib "eagle-import") (part "ATMEGA328PBTQFP-32"))
    )
    (comp (ref "X1")
      (value "JST-XH-06-PIN-LONG-PAD")
      (footprint "eagle-import:JST-XH-06-PACKAGE-LONG-PAD")
      (libsource (lib "eagle-import") (part "JST-XH-06-PIN-LONG-PAD"))
    )
    (comp (ref "X2")
      (value "JST-XH-06-PIN-LONG-PAD")
      (footprint "eagle-import:JST-XH-06-PACKAGE-LONG-PAD")
      (libsource (lib "eagle-import") (part "JST-XH-06-PIN-LONG-PAD"))
    )
    (comp (ref "X3")
      (value "JST-XH-07-PIN-LONG-PAD")
      (footprint "eagle-import:JST-XH-07-PACKAGE-LONG-PAD")
      (libsource (lib "eagle-import") (part "JST-XH-07-PIN-LONG-PAD"))
    )
    (comp (ref "X4")
      (value "JST-XH-06-PIN-LONG-PAD")
      (footprint "eagle-import:JST-XH-06-PACKAGE-LONG-PAD")
      (libsource (lib "eagle-import") (part "JST-XH-06-PIN-LONG-PAD"))
    )
    (comp (ref "X5")
      (value "JST-XH-06-PIN-LONG-PAD")
      (footprint "eagle-import:JST-XH-06-PACKAGE-LONG-PAD")
      (libsource (lib "eagle-import") (part "JST-XH-06-PIN-LONG-PAD"))
    )
  )
  (nets
    (net (code "2") (name "+5V") (class "Default")
      (node (ref "C10") (pin "+") (pinfunction "+_+") (pintype "passive"))
      (node (ref "C13") (pin "2") (pinfunction "2_2") (pintype "passive"))
      (node (ref "C14") (pin "2") (pinfunction "2_2") (pintype "passive"))
      (node (ref "C15") (pin "1") (pinfunction "1_1") (pintype "passive"))
      (node (ref "C4") (pin "2") (pinfunction "2_2") (pintype "passive"))
      (node (ref "C6") (pin "1") (pinfunction "1_1") (pintype "passive"))
      (node (ref "C7") (pin "1") (pinfunction "1_1") (pintype "passive"))
      (node (ref "IC1") (pin "16") (pinfunction "VCC_16") (pintype "power_in"))
      (node (ref "IC2") (pin "16") (pinfunction "VCC_16") (pintype "power_in"))
      (node (ref "ISP1") (pin "2") (pinfunction "VCC_2") (pintype "power_in"))
      (node (ref "J1") (pin "VCC") (pinfunction "4_VCC") (pintype "passive"))
      (node (ref "JP10") (pin "1") (pinfunction "1_1") (pintype "passive"))
      (node (ref "R1") (pin "2") (pinfunction "2_2") (pintype "passive"))
      (node (ref "R2") (pin "2") (pinfunction "2_2") (pintype "passive"))
      (node (ref "R4") (pin "2") (pinfunction "2_2") (pintype "passive"))
      (node (ref "R58") (pin "2") (pinfunction "2_2") (pintype "passive"))
      (node (ref "R6") (pin "2") (pinfunction "2_2") (pintype "passive"))
      (node (ref "R61") (pin "1") (pinfunction "1_1") (pintype "passive"))
      (node (ref "SJ3") (pin "1") (pinfunction "1_1") (pintype "passive"))
      (node (ref "U1") (pin "18") (pinfunction "AVCC_18") (pintype "power_in"))
      (node (ref "U1") (pin "20") (pinfunction "AREF_20") (pintype "power_in"))
      (node (ref "U1") (pin "4") (pinfunction "VCC_4") (pintype "power_in"))
      (node (ref "U2") (pin "14") (pinfunction "VCC_14") (pintype "bidirectional"))
      (node (ref "U3") (pin "1") (pinfunction "SHDWN_1") (pintype "bidirectional"))
      (node (ref "U3") (pin "6") (pinfunction "VDD_6") (pintype "bidirectional"))
      (node (ref "U4") (pin "10") (pinfunction "VLOGIC_10") (pintype "bidirectional"))
      (node (ref "U4") (pin "13") (pinfunction "WP_13") (pintype "bidirectional"))
      (node (ref "U4") (pin "16") (pinfunction "LRDAC_16") (pintype "bidirectional"))
      (node (ref "U4") (pin "9") (pinfunction "VDD_9") (pintype "bidirectional"))
      (node (ref "X3") (pin "1") (pinfunction "S_1") (pintype "passive"))
    )
    (net (code "3") (name "+12V") (class "Default")
      (node (ref "C16") (pin "+") (pinfunction "+_+") (pintype "passive"))
      (node (ref "IC3") (pin "1") (pinfunction "IN_1") (pintype "input"))
      (node (ref "JP10") (pin "2") (pinfunction "2_2") (pintype "passive"))
      (node (ref "Q11") (pin "2") (pinfunction "S_2") (pintype "passive"))
      (node (ref "Q12") (pin "2") (pinfunction "S_2") (pintype "passive"))
      (node (ref "Q13") (pin "2") (pinfunction "S_2") (pintype "passive"))
      (node (ref "Q17") (pin "2") (pinfunction "S_2") (pintype "passive"))
      (node (ref "Q18") (pin "2") (pinfunction "S_2") (pintype "passive"))
      (node (ref "Q19") (pin "2") (pinfunction "S_2") (pintype "passive"))
      (node (ref "Q5") (pin "2") (pinfunction "S_2") (pintype "passive"))
      (node (ref "Q6") (pin "2") (pinfunction "S_2") (pintype "passive"))
      (node (ref "Q7") (pin "2") (pinfunction "S_2") (pintype "passive"))
      (node (ref "R13") (pin "2") (pinfunction "2_2") (pintype "passive"))
      (node (ref "R14") (pin "2") (pinfunction "2_2") (pintype "passive"))
      (node (ref "R15") (pin "2") (pinfunction "2_2") (pintype "passive"))
      (node (ref "R25") (pin "2") (pinfunction "2_2") (pintype "passive"))
      (node (ref "R26") (pin "2") (pinfunction "2_2") (pintype "passive"))
      (node (ref "R27") (pin "2") (pinfunction "2_2") (pintype "passive"))
      (node (ref "R37") (pin "2") (pinfunction "2_2") (pintype "passive"))
      (node (ref "R38") (pin "2") (pinfunction "2_2") (pintype "passive"))
      (node (ref "R39") (pin "2") (pinfunction "2_2") (pintype "passive"))
      (node (ref "SJ1") (pin "2") (pinfunction "2_2") (pintype "passive"))
      (node (ref "SJ2") (pin "3") (pinfunction "3_3") (pintype "passive"))
      (node (ref "X18") (pin "1") (pinfunction "S_1") (pintype "passive"))
      (node (ref "X18") (pin "2") (pinfunction "S_2") (pintype "passive"))
      (node (ref "X19") (pin "1") (pinfunction "S_1") (pintype "passive"))
      (node (ref "X19") (pin "2") (pinfunction "S_2") (pintype "passive"))
      (node (ref "X20") (pin "1") (pinfunction "S_1") (pintype "passive"))
      (node (ref "X20") (pin "2") (pinfunction "S_2") (pintype "passive"))
      (node (ref "X21") (pin "1") (pinfunction "S_1") (pintype "passive"))
      (node (ref "X21") (pin "2") (pinfunction "S_2") (pintype "passive"))
    )
    (net (code "5") (name "A") (class "Default")
      (node (ref "Q20") (pin "3") (pinfunction "D_3") (pintype "bidirectional"))
      (node (ref "X10") (pin "5") (pinfunction "S_5") (pintype "passive"))
      (node (ref "X11") (pin "5") (pinfunction "S_5") (pintype "passive"))
      (node (ref "X12") (pin "5") (pinfunction "S_5") (pintype "passive"))
      (node (ref "X13") (pin "5") (pinfunction "S_5") (pintype "passive"))
      (node (ref "X14") (pin "5") (pinfunction "S_5") (pintype "passive"))
      (node (ref "X6") (pin "5") (pinfunction "S_5") (pintype "passive"))
      (node (ref "X7") (pin "5") (pinfunction "S_5") (pintype "passive"))
      (node (ref "X8") (pin "5") (pinfunction "S_5") (pintype "passive"))
      (node (ref "X9") (pin "5") (pinfunction "S_5") (pintype "passive"))
    )
    (net (code "6") (name "ADSOUND+") (class "Default")
      (node (ref "SJ4") (pin "1") (pinfunction "1_1") (pintype "passive"))
      (node (ref "U3") (pin "5") (pinfunction "OUT+_5") (pintype "bidirectional"))
    )
    (net (code "7") (name "ADSOUND-") (class "Default")
      (node (ref "SJ5") (pin "3") (pinfunction "3_3") (pintype "passive"))
      (node (ref "U3") (pin "8") (pinfunction "OUT-_8") (pintype "bidirectional"))
    )
    (net (code "8") (name "AN1") (class "Default")
      (node (ref "IC1") (pin "7") (pinfunction "QH_7") (pintype "tri_state"))
      (node (ref "R7") (pin "1") (pinfunction "1_1") (pintype "passive"))
    )
    (net (code "9") (name "AN2") (class "Default")
      (node (ref "IC2") (pin "15") (pinfunction "QA_15") (pintype "tri_state"))
      (node (ref "R19") (pin "1") (pinfunction "1_1") (pintype "passive"))
    )
    (net (code "10") (name "AN3") (class "Default")
      (node (ref "IC2") (pin "1") (pinfunction "QB_1") (pintype "tri_state"))
      (node (ref "R31") (pin "1") (pinfunction "1_1") (pintype "passive"))
    )
    (net (code "11") (name "AN4") (class "Default")
      (node (ref "IC2") (pin "2") (pinfunction "QC_2") (pintype "tri_state"))
      (node (ref "R8") (pin "1") (pinfunction "1_1") (pintype "passive"))
    )
    (net (code "12") (name "AN5") (class "Default")
      (node (ref "IC2") (pin "3") (pinfunction "QD_3") (pintype "tri_state"))
      (node (ref "R20") (pin "1") (pinfunction "1_1") (pintype "passive"))
    )
    (net (code "13") (name "AN6") (class "Default")
      (node (ref "IC2") (pin "4") (pinfunction "QE_4") (pintype "tri_state"))
      (node (ref "R32") (pin "1") (pinfunction "1_1") (pintype "passive"))
    )
    (net (code "14") (name "AN7") (class "Default")
      (node (ref "IC2") (pin "5") (pinfunction "QF_5") (pintype "tri_state"))
      (node (ref "R9") (pin "1") (pinfunction "1_1") (pintype "passive"))
    )
    (net (code "15") (name "AN8") (class "Default")
      (node (ref "IC2") (pin "6") (pinfunction "QG_6") (pintype "tri_state"))
      (node (ref "R21") (pin "1") (pinfunction "1_1") (pintype "passive"))
    )
    (net (code "16") (name "AN9") (class "Default")
      (node (ref "IC2") (pin "7") (pinfunction "QH_7") (pintype "tri_state"))
      (node (ref "R33") (pin "1") (pinfunction "1_1") (pintype "passive"))
    )
    (net (code "17") (name "B") (class "Default")
      (node (ref "Q21") (pin "3") (pinfunction "D_3") (pintype "bidirectional"))
      (node (ref "X10") (pin "6") (pinfunction "S_6") (pintype "passive"))
      (node (ref "X11") (pin "6") (pinfunction "S_6") (pintype "passive"))
      (node (ref "X12") (pin "6") (pinfunction "S_6") (pintype "passive"))
      (node (ref "X13") (pin "6") (pinfunction "S_6") (pintype "passive"))
      (node (ref "X14") (pin "6") (pinfunction "S_6") (pintype "passive"))
      (node (ref "X6") (pin "6") (pinfunction "S_6") (pintype "passive"))
      (node (ref "X7") (pin "6") (pinfunction "S_6") (pintype "passive"))
      (node (ref "X8") (pin "6") (pinfunction "S_6") (pintype "passive"))
      (node (ref "X9") (pin "6") (pinfunction "S_6") (pintype "passive"))
    )
    (net (code "18") (name "B_COL_0") (class "Default")
      (node (ref "U1") (pin "32") (pinfunction "PD2_32") (pintype "bidirectional"))
      (node (ref "X1") (pin "4") (pinfunction "S_4") (pintype "passive"))
      (node (ref "X2") (pin "4") (pinfunction "S_4") (pintype "passive"))
    )
    (net (code "19") (name "B_COL_1") (class "Default")
      (node (ref "U1") (pin "1") (pinfunction "PD3_1") (pintype "bidirectional"))
      (node (ref "X1") (pin "5") (pinfunction "S_5") (pintype "passive"))
      (node (ref "X2") (pin "5") (pinfunction "S_5") (pintype "passive"))
    )
    (net (code "20") (name "B_COL_2") (class "Default")
      (node (ref "U1") (pin "2") (pinfunction "PD4_2") (pintype "bidirectional"))
      (node (ref "X1") (pin "6") (pinfunction "S_6") (pintype "passive"))
      (node (ref "X2") (pin "6") (pinfunction "S_6") (pintype "passive"))
    )
    (net (code "21") (name "B_COL_3") (class "Default")
      (node (ref "U1") (pin "9") (pinfunction "PD5_9") (pintype "bidirectional"))
      (node (ref "X4") (pin "4") (pinfunction "S_4") (pintype "passive"))
      (node (ref "X5") (pin "4") (pinfunction "S_4") (pintype "passive"))
    )
    (net (code "22") (name "B_COL_4") (class "Default")
      (node (ref "U1") (pin "10") (pinfunction "PD6_10") (pintype "bidirectional"))
      (node (ref "X4") (pin "5") (pinfunction "S_5") (pintype "passive"))
      (node (ref "X5") (pin "5") (pinfunction "S_5") (pintype "passive"))
    )
    (net (code "23") (name "B_COL_5") (class "Default")
      (node (ref "U1") (pin "11") (pinfunction "PD7_11") (pintype "bidirectional"))
      (node (ref "X4") (pin "6") (pinfunction "S_6") (pintype "passive"))
      (node (ref "X5") (pin "6") (pinfunction "S_6") (pintype "passive"))
    )
    (net (code "24") (name "B_ROW_0") (class "Default")
      (node (ref "U1") (pin "23") (pinfunction "PC0_23") (pintype "bidirectional"))
      (node (ref "X1") (pin "1") (pinfunction "S_1") (pintype "passive"))
      (node (ref "X4") (pin "1") (pinfunction "S_1") (pintype "passive"))
    )
    (net (code "25") (name "B_ROW_1") (class "Default")
      (node (ref "U1") (pin "24") (pinfunction "PC1_24") (pintype "bidirectional"))
      (node (ref "X1") (pin "2") (pinfunction "S_2") (pintype "passive"))
      (node (ref "X4") (pin "2") (pinfunction "S_2") (pintype "passive"))
    )
    (net (code "26") (name "B_ROW_2") (class "Default")
      (node (ref "U1") (pin "25") (pinfunction "PC2_25") (pintype "bidirectional"))
      (node (ref "X1") (pin "3") (pinfunction "S_3") (pintype "passive"))
      (node (ref "X4") (pin "3") (pinfunction "S_3") (pintype "passive"))
    )
    (net (code "27") (name "B_ROW_3") (class "Default")
      (node (ref "U1") (pin "26") (pinfunction "PC3_26") (pintype "bidirectional"))
      (node (ref "X2") (pin "1") (pinfunction "S_1") (pintype "passive"))
      (node (ref "X5") (pin "1") (pinfunction "S_1") (pintype "passive"))
    )
    (net (code "28") (name "B_ROW_4") (class "Default")
      (node (ref "U1") (pin "27") (pinfunction "PC4_27") (pintype "bidirectional"))
      (node (ref "X2") (pin "2") (pinfunction "S_2") (pintype "passive"))
      (node (ref "X5") (pin "2") (pinfunction "S_2") (pintype "passive"))
    )
    (net (code "29") (name "B_ROW_5") (class "Default")
      (node (ref "U1") (pin "28") (pinfunction "PC5_28") (pintype "bidirectional"))
      (node (ref "X2") (pin "3") (pinfunction "S_3") (pintype "passive"))
      (node (ref "X5") (pin "3") (pinfunction "S_3") (pintype "passive"))
    )
    (net (code "30") (name "C") (class "Default")
      (node (ref "Q22") (pin "3") (pinfunction "D_3") (pintype "bidirectional"))
      (node (ref "X10") (pin "7") (pinfunction "S_7") (pintype "passive"))
      (node (ref "X11") (pin "7") (pinfunction "S_7") (pintype "passive"))
      (node (ref "X12") (pin "7") (pinfunction "S_7") (pintype "passive"))
      (node (ref "X13") (pin "7") (pinfunction "S_7") (pintype "passive"))
      (node (ref "X14") (pin "7") (pinfunction "S_7") (pintype "passive"))
      (node (ref "X6") (pin "7") (pinfunction "S_7") (pintype "passive"))
      (node (ref "X7") (pin "7") (pinfunction "S_7") (pintype "passive"))
      (node (ref "X8") (pin "7") (pinfunction "S_7") (pintype "passive"))
      (node (ref "X9") (pin "7") (pinfunction "S_7") (pintype "passive"))
    )
    (net (code "31") (name "D") (class "Default")
      (node (ref "Q23") (pin "3") (pinfunction "D_3") (pintype "bidirectional"))
      (node (ref "X10") (pin "1") (pinfunction "S_1") (pintype "passive"))
      (node (ref "X11") (pin "1") (pinfunction "S_1") (pintype "passive"))
      (node (ref "X12") (pin "1") (pinfunction "S_1") (pintype "passive"))
      (node (ref "X13") (pin "1") (pinfunction "S_1") (pintype "passive"))
      (node (ref "X14") (pin "1") (pinfunction "S_1") (pintype "passive"))
      (node (ref "X6") (pin "1") (pinfunction "S_1") (pintype "passive"))
      (node (ref "X7") (pin "1") (pinfunction "S_1") (pintype "passive"))
      (node (ref "X8") (pin "1") (pinfunction "S_1") (pintype "passive"))
      (node (ref "X9") (pin "1") (pinfunction "S_1") (pintype "passive"))
    )
    (net (code "32") (name "D+") (class "Default")
      (node (ref "JP5") (pin "3") (pinfunction "3_3") (pintype "passive"))
      (node (ref "R58") (pin "1") (pinfunction "1_1") (pintype "passive"))
      (node (ref "R59") (pin "2") (pinfunction "2_2") (pintype "passive"))
      (node (ref "R60") (pin "2") (pinfunction "2_2") (pintype "passive"))
      (node (ref "U$1") (pin "P$3") (pinfunction "D+_P$3") (pintype "bidirectional"))
    )
    (net (code "33") (name "D-") (class "Default")
      (node (ref "JP5") (pin "2") (pinfunction "2_2") (pintype "passive"))
      (node (ref "R61") (pin "2") (pinfunction "2_2") (pintype "passive"))
      (node (ref "R62") (pin "1") (pinfunction "1_1") (pintype "passive"))
      (node (ref "R63") (pin "1") (pinfunction "1_1") (pintype "passive"))
      (node (ref "U$1") (pin "P$2") (pinfunction "D-_P$2") (pintype "bidirectional"))
    )
    (net (code "34") (name "DTR") (class "Default")
      (node (ref "C1") (pin "2") (pinfunction "2_2") (pintype "passive"))
      (node (ref "J1") (pin "DTR") (pinfunction "1_DTR") (pintype "passive"))
    )
    (net (code "35") (name "E") (class "Default")
      (node (ref "Q24") (pin "3") (pinfunction "D_3") (pintype "bidirectional"))
      (node (ref "X10") (pin "2") (pinfunction "S_2") (pintype "passive"))
      (node (ref "X11") (pin "2") (pinfunction "S_2") (pintype "passive"))
      (node (ref "X12") (pin "2") (pinfunction "S_2") (pintype "passive"))
      (node (ref "X13") (pin "2") (pinfunction "S_2") (pintype "passive"))
      (node (ref "X14") (pin "2") (pinfunction "S_2") (pintype "passive"))
      (node (ref "X6") (pin "2") (pinfunction "S_2") (pintype "passive"))
      (node (ref "X7") (pin "2") (pinfunction "S_2") (pintype "passive"))
      (node (ref "X8") (pin "2") (pinfunction "S_2") (pintype "passive"))
      (node (ref "X9") (pin "2") (pinfunction "S_2") (pintype "passive"))
    )
    (net (code "36") (name "F") (class "Default")
      (node (ref "Q25") (pin "3") (pinfunction "D_3") (pintype "bidirectional"))
      (node (ref "X10") (pin "4") (pinfunction "S_4") (pintype "passive"))
      (node (ref "X11") (pin "4") (pinfunction "S_4") (pintype "passive"))
      (node (ref "X12") (pin "4") (pinfunction "S_4") (pintype "passive"))
      (node (ref "X13") (pin "4") (pinfunction "S_4") (pintype "passive"))
      (node (ref "X14") (pin "4") (pinfunction "S_4") (pintype "passive"))
      (node (ref "X6") (pin "4") (pinfunction "S_4") (pintype "passive"))
      (node (ref "X7") (pin "4") (pinfunction "S_4") (pintype "passive"))
      (node (ref "X8") (pin "4") (pinfunction "S_4") (pintype "passive"))
      (node (ref "X9") (pin "4") (pinfunction "S_4") (pintype "passive"))
    )
    (net (code "37") (name "FTDIRX") (class "Default")
      (node (ref "J1") (pin "TXO") (pinfunction "3_TXO") (pintype "passive"))
      (node (ref "JP1") (pin "2") (pinfunction "2_2") (pintype "passive"))
    )
    (net (code "38") (name "FTDITX") (class "Default")
      (node (ref "J1") (pin "RXI") (pinfunction "2_RXI") (pintype "passive"))
      (node (ref "JP2") (pin "2") (pinfunction "2_2") (pintype "passive"))
    )
    (net (code "39") (name "G") (class "Default")
      (node (ref "Q26") (pin "3") (pinfunction "D_3") (pintype "bidirectional"))
      (node (ref "X10") (pin "3") (pinfunction "S_3") (pintype "passive"))
      (node (ref "X11") (pin "3") (pinfunction "S_3") (pintype "passive"))
      (node (ref "X12") (pin "3") (pinfunction "S_3") (pintype "passive"))
      (node (ref "X13") (pin "3") (pinfunction "S_3") (pintype "passive"))
      (node (ref "X14") (pin "3") (pinfunction "S_3") (pintype "passive"))
      (node (ref "X6") (pin "3") (pinfunction "S_3") (pintype "passive"))
      (node (ref "X7") (pin "3") (pinfunction "S_3") (pintype "passive"))
      (node (ref "X8") (pin "3") (pinfunction "S_3") (pintype "passive"))
      (node (ref "X9") (pin "3") (pinfunction "S_3") (pintype "passive"))
    )
    (net (code "40") (name "GND") (class "Default")
      (node (ref "C10") (pin "-") (pinfunction "-_-") (pintype "passive"))
      (node (ref "C11") (pin "2") (pinfunction "2_2") (pintype "passive"))
      (node (ref "C13") (pin "1") (pinfunction "1_1") (pintype "passive"))
      (node (ref "C14") (pin "1") (pinfunction "1_1") (pintype "passive"))
      (node (ref "C15") (pin "2") (pinfunction "2_2") (pintype "passive"))
      (node (ref "C16") (pin "-") (pinfunction "-_-") (pintype "passive"))
      (node (ref "C17") (pin "-") (pinfunction "-_-") (pintype "passive"))
      (node (ref "C2") (pin "1") (pinfunction "1_1") (pintype "passive"))
      (node (ref "C3") (pin "1") (pinfunction "1_1") (pintype "passive"))
      (node (ref "C4") (pin "1") (pinfunction "1_1") (pintype "passive"))
      (node (ref "C5") (pin "1") (pinfunction "1_1") (pintype "passive"))
      (node (ref "C6") (pin "2") (pinfunction "2_2") (pintype "passive"))
      (node (ref "C7") (pin "2") (pinfunction "2_2") (pintype "passive"))
      (node (ref "C9") (pin "1") (pinfunction "1_1") (pintype "passive"))
      (node (ref "D1") (pin "A") (pinfunction "A_A") (pintype "passive"))
      (node (ref "IC1") (pin "8") (pinfunction "GND_8") (pintype "power_in"))
      (node (ref "IC2") (pin "8") (pinfunction "GND_8") (pintype "power_in"))
      (node (ref "IC3") (pin "3") (pinfunction "GND_3") (pintype "power_in"))
      (node (ref "IC3") (pin "6") (pinfunction "GND_6") (pintype "power_in"))
      (node (ref "ISP1") (pin "6") (pinfunction "GND_6") (pintype "power_in"))
      (node (ref "J1") (pin "CTS") (pinfunction "5_CTS") (pintype "passive"))
      (node (ref "J1") (pin "GND") (pinfunction "6_GND") (pintype "passive"))
      (node (ref "JP10") (pin "3") (pinfunction "3_3") (pintype "passive"))
      (node (ref "JP5") (pin "5") (pinfunction "5_5") (pintype "passive"))
      (node (ref "JP6") (pin "1") (pinfunction "1_1") (pintype "passive"))
      (node (ref "JP6") (pin "2") (pinfunction "2_2") (pintype "passive"))
      (node (ref "JP6") (pin "3") (pinfunction "3_3") (pintype "passive"))
      (node (ref "JP6") (pin "4") (pinfunction "4_4") (pintype "passive"))
      (node (ref "Q10") (pin "2") (pinfunction "S_2") (pintype "bidirectional"))
      (node (ref "Q14") (pin "2") (pinfunction "S_2") (pintype "bidirectional"))
      (node (ref "Q15") (pin "2") (pinfunction "S_2") (pintype "bidirectional"))
      (node (ref "Q16") (pin "2") (pinfunction "S_2") (pintype "bidirectional"))
      (node (ref "Q2") (pin "2") (pinfunction "S_2") (pintype "bidirectional"))
      (node (ref "Q20") (pin "2") (pinfunction "S_2") (pintype "bidirectional"))
      (node (ref "Q21") (pin "2") (pinfunction "S_2") (pintype "bidirectional"))
      (node (ref "Q22") (pin "2") (pinfunction "S_2") (pintype "bidirectional"))
      (node (ref "Q23") (pin "2") (pinfunction "S_2") (pintype "bidirectional"))
      (node (ref "Q24") (pin "2") (pinfunction "S_2") (pintype "bidirectional"))
      (node (ref "Q25") (pin "2") (pinfunction "S_2") (pintype "bidirectional"))
      (node (ref "Q26") (pin "2") (pinfunction "S_2") (pintype "bidirectional"))
      (node (ref "Q3") (pin "2") (pinfunction "S_2") (pintype "bidirectional"))
      (node (ref "Q4") (pin "2") (pinfunction "S_2") (pintype "bidirectional"))
      (node (ref "Q8") (pin "2") (pinfunction "S_2") (pintype "bidirectional"))
      (node (ref "Q9") (pin "2") (pinfunction "S_2") (pintype "bidirectional"))
      (node (ref "R10") (pin "1") (pinfunction "1_1") (pintype "passive"))
      (node (ref "R11") (pin "1") (pinfunction "1_1") (pintype "passive"))
      (node (ref "R12") (pin "1") (pinfunction "1_1") (pintype "passive"))
      (node (ref "R16") (pin "1") (pinfunction "1_1") (pintype "passive"))
      (node (ref "R17") (pin "1") (pinfunction "1_1") (pintype "passive"))
      (node (ref "R18") (pin "1") (pinfunction "1_1") (pintype "passive"))
      (node (ref "R22") (pin "1") (pinfunction "1_1") (pintype "passive"))
      (node (ref "R23") (pin "1") (pinfunction "1_1") (pintype "passive"))
      (node (ref "R24") (pin "1") (pinfunction "1_1") (pintype "passive"))
      (node (ref "R28") (pin "1") (pinfunction "1_1") (pintype "passive"))
      (node (ref "R29") (pin "1") (pinfunction "1_1") (pintype "passive"))
      (node (ref "R3") (pin "1") (pinfunction "1_1") (pintype "passive"))
      (node (ref "R30") (pin "1") (pinfunction "1_1") (pintype "passive"))
      (node (ref "R34") (pin "1") (pinfunction "1_1") (pintype "passive"))
      (node (ref "R35") (pin "1") (pinfunction "1_1") (pintype "passive"))
      (node (ref "R36") (pin "1") (pinfunction "1_1") (pintype "passive"))
      (node (ref "R40") (pin "1") (pinfunction "1_1") (pintype "passive"))
      (node (ref "R41") (pin "1") (pinfunction "1_1") (pintype "passive"))
      (node (ref "R42") (pin "1") (pinfunction "1_1") (pintype "passive"))
      (node (ref "R48") (pin "1") (pinfunction "1_1") (pintype "passive"))
      (node (ref "R49") (pin "1") (pinfunction "1_1") (pintype "passive"))
      (node (ref "R50") (pin "1") (pinfunction "1_1") (pintype "passive"))
      (node (ref "R51") (pin "1") (pinfunction "1_1") (pintype "passive"))
      (node (ref "R52") (pin "1") (pinfunction "1_1") (pintype "passive"))
      (node (ref "R55") (pin "1") (pinfunction "1_1") (pintype "passive"))
      (node (ref "R56") (pin "1") (pinfunction "1_1") (pintype "passive"))
      (node (ref "R57") (pin "1") (pinfunction "1_1") (pintype "passive"))
      (node (ref "R59") (pin "1") (pinfunction "1_1") (pintype "passive"))
      (node (ref "R62") (pin "2") (pinfunction "2_2") (pintype "passive"))
      (node (ref "RESET") (pin "1") (pinfunction "A1_1") (pintype "bidirectional"))
      (node (ref "SJ2") (pin "1") (pinfunction "1_1") (pintype "passive"))
      (node (ref "SJ5") (pin "1") (pinfunction "1_1") (pintype "passive"))
      (node (ref "U$1") (pin "P$5") (pinfunction "GND_P$5") (pintype "bidirectional"))
      (node (ref "U$1") (pin "P$6") (pinfunction "GND_P$6") (pintype "bidirectional"))
      (node (ref "U$1") (pin "P$8") (pinfunction "GND_P$8") (pintype "bidirectional"))
      (node (ref "U1") (pin "21") (pinfunction "GND_21") (pintype "power_in"))
      (node (ref "U1") (pin "5") (pinfunction "GND_5") (pintype "power_in"))
      (node (ref "U2") (pin "10") (pinfunction "GND_10") (pintype "bidirectional"))
      (node (ref "U2") (pin "11") (pinfunction "GND_11") (pintype "bidirectional"))
      (node (ref "U2") (pin "12") (pinfunction "GND_12") (pintype "bidirectional"))
      (node (ref "U2") (pin "3") (pinfunction "GND_3") (pintype "bidirectional"))
      (node (ref "U2") (pin "4") (pinfunction "GND_4") (pintype "bidirectional"))
      (node (ref "U2") (pin "5") (pinfunction "GND_5") (pintype "bidirectional"))
      (node (ref "U2") (pin "6") (pinfunction "IN-_6") (pintype "bidirectional"))
      (node (ref "U2") (pin "7") (pinfunction "GND_7") (pintype "bidirectional"))
      (node (ref "U3") (pin "7") (pinfunction "GND_7") (pintype "bidirectional"))
      (node (ref "U4") (pin "1") (pinfunction "GND_1") (pintype "power_in"))
      (node (ref "U4") (pin "15") (pinfunction "INDEP_15") (pintype "bidirectional"))
      (node (ref "U4") (pin "17") (pinfunction "VSS_17") (pintype "power_in"))
      (node (ref "U4") (pin "5") (pinfunction "VSS_5") (pintype "power_in"))
      (node (ref "U4") (pin "7") (pinfunction "RESET_7") (pintype "bidirectional"))
      (node (ref "U4") (pin "8") (pinfunction "DIS_8") (pintype "bidirectional"))
      (node (ref "X22") (pin "1") (pinfunction "S_1") (pintype "passive"))
      (node (ref "X22") (pin "2") (pinfunction "S_2") (pintype "passive"))
      (node (ref "X22") (pin "3") (pinfunction "S_3") (pintype "passive"))
      (node (ref "X23") (pin "1") (pinfunction "S_1") (pintype "passive"))
      (node (ref "X23") (pin "2") (pinfunction "S_2") (pintype "passive"))
      (node (ref "X23") (pin "3") (pinfunction "S_3") (pintype "passive"))
      (node (ref "X24") (pin "1") (pinfunction "S_1") (pintype "passive"))
      (node (ref "X24") (pin "2") (pinfunction "S_2") (pintype "passive"))
      (node (ref "X24") (pin "3") (pinfunction "S_3") (pintype "passive"))
      (node (ref "X25") (pin "1") (pinfunction "S_1") (pintype "passive"))
      (node (ref "X25") (pin "2") (pinfunction "S_2") (pintype "passive"))
      (node (ref "X25") (pin "3") (pinfunction "S_3") (pintype "passive"))
      (node (ref "X3") (pin "7") (pinfunction "S_7") (pintype "passive"))
    )
    (net (code "41") (name "LED_B") (class "Default")
      (node (ref "IC1") (pin "10") (pinfunction "SCL_10") (pintype "input"))
      (node (ref "IC2") (pin "10") (pinfunction "SCL_10") (pintype "input"))
      (node (ref "R2") (pin "1") (pinfunction "1_1") (pintype "passive"))
      (node (ref "U1") (pin "22") (pinfunction "PE3_22") (pintype "bidirectional"))
      (node (ref "X3") (pin "5") (pinfunction "S_5") (pintype "passive"))
    )
    (net (code "42") (name "LED_D_OUT") (class "Default")
      (node (ref "IC2") (pin "9") (pinfunction "QH*_9") (pintype "tri_state"))
      (node (ref "X3") (pin "2") (pinfunction "S_2") (pintype "passive"))
    )
    (net (code "43") (name "LED_L") (class "Default")
      (node (ref "IC1") (pin "12") (pinfunction "RCK_12") (pintype "input"))
      (node (ref "IC2") (pin "12") (pinfunction "RCK_12") (pintype "input"))
      (node (ref "R1") (pin "1") (pinfunction "1_1") (pintype "passive"))
      (node (ref "U1") (pin "12") (pinfunction "PB0_12") (pintype "bidirectional"))
      (node (ref "X3") (pin "4") (pinfunction "S_4") (pintype "passive"))
    )
    (net (code "44") (name "LED_O") (class "Default")
      (node (ref "IC1") (pin "13") (pinfunction "G_13") (pintype "input"))
      (node (ref "IC2") (pin "13") (pinfunction "G_13") (pintype "input"))
      (node (ref "R3") (pin "2") (pinfunction "2_2") (pintype "passive"))
      (node (ref "U1") (pin "19") (pinfunction "PE2_19") (pintype "bidirectional"))
      (node (ref "X3") (pin "6") (pinfunction "S_6") (pintype "passive"))
    )
    (net (code "45") (name "LMSOUND") (class "Default")
      (node (ref "C12") (pin "-") (pinfunction "-_-") (pintype "passive"))
      (node (ref "SJ4") (pin "3") (pinfunction "3_3") (pintype "passive"))
    )
    (net (code "46") (name "MISO") (class "Default")
      (node (ref "ISP1") (pin "1") (pinfunction "MISO_1") (pintype "input"))
      (node (ref "U1") (pin "16") (pinfunction "PB4_16") (pintype "bidirectional"))
      (node (ref "U4") (pin "14") (pinfunction "SDO_AD1_14") (pintype "bidirectional"))
    )
    (net (code "47") (name "MOSI") (class "Default")
      (node (ref "IC1") (pin "14") (pinfunction "SER_14") (pintype "input"))
      (node (ref "ISP1") (pin "4") (pinfunction "MOSI_4") (pintype "output"))
      (node (ref "U1") (pin "15") (pinfunction "PB3_15") (pintype "bidirectional"))
      (node (ref "U4") (pin "12") (pinfunction "SDI_SDA_12") (pintype "bidirectional"))
    )
    (net (code "48") (name "Net-(IC1A-QH*)") (class "Default")
      (node (ref "IC1") (pin "9") (pinfunction "QH*_9") (pintype "tri_state"))
      (node (ref "IC2") (pin "14") (pinfunction "SER_14") (pintype "input"))
    )
    (net (code "49") (name "Net-(IC3-EN)") (class "Default")
      (node (ref "IC3") (pin "5") (pinfunction "EN_5") (pintype "input"))
      (node (ref "SJ2") (pin "2") (pinfunction "2_2") (pintype "passive"))
    )
    (net (code "50") (name "Net-(IC3-FB)") (class "Default")
      (node (ref "C17") (pin "+") (pinfunction "+_+") (pintype "passive"))
      (node (ref "IC3") (pin "4") (pinfunction "FB_4") (pintype "input"))
      (node (ref "L1") (pin "P$2") (pinfunction "2_P$2") (pintype "passive"))
      (node (ref "SJ3") (pin "2") (pinfunction "2_2") (pintype "passive"))
    )
    (net (code "51") (name "Net-(IC3-OUT)") (class "Default")
      (node (ref "D1") (pin "C") (pinfunction "C_C") (pintype "passive"))
      (node (ref "IC3") (pin "2") (pinfunction "OUT_2") (pintype "output"))
      (node (ref "L1") (pin "P$1") (pinfunction "1_P$1") (pintype "passive"))
    )
    (net (code "52") (name "Net-(Q2-D)") (class "Default")
      (node (ref "Q2") (pin "3") (pinfunction "D_3") (pintype "bidirectional"))
      (node (ref "Q5") (pin "1") (pinfunction "G_1") (pintype "passive"))
      (node (ref "R13") (pin "1") (pinfunction "1_1") (pintype "passive"))
    )
    (net (code "53") (name "Net-(Q2-G)") (class "Default")
      (node (ref "Q2") (pin "1") (pinfunction "G_1") (pintype "bidirectional"))
      (node (ref "R10") (pin "2") (pinfunction "2_2") (pintype "passive"))
      (node (ref "R7") (pin "2") (pinfunction "2_2") (pintype "passive"))
    )
    (net (code "54") (name "Net-(Q3-D)") (class "Default")
      (node (ref "Q3") (pin "3") (pinfunction "D_3") (pintype "bidirectional"))
      (node (ref "Q6") (pin "1") (pinfunction "G_1") (pintype "passive"))
      (node (ref "R14") (pin "1") (pinfunction "1_1") (pintype "passive"))
    )
    (net (code "55") (name "Net-(Q3-G)") (class "Default")
      (node (ref "Q3") (pin "1") (pinfunction "G_1") (pintype "bidirectional"))
      (node (ref "R11") (pin "2") (pinfunction "2_2") (pintype "passive"))
      (node (ref "R8") (pin "2") (pinfunction "2_2") (pintype "passive"))
    )
    (net (code "56") (name "Net-(Q4-D)") (class "Default")
      (node (ref "Q4") (pin "3") (pinfunction "D_3") (pintype "bidirectional"))
      (node (ref "Q7") (pin "1") (pinfunction "G_1") (pintype "passive"))
      (node (ref "R15") (pin "1") (pinfunction "1_1") (pintype "passive"))
    )
    (net (code "57") (name "Net-(Q4-G)") (class "Default")
      (node (ref "Q4") (pin "1") (pinfunction "G_1") (pintype "bidirectional"))
      (node (ref "R12") (pin "2") (pinfunction "2_2") (pintype "passive"))
      (node (ref "R9") (pin "2") (pinfunction "2_2") (pintype "passive"))
    )
    (net (code "58") (name "Net-(Q8-G)") (class "Default")
      (node (ref "Q8") (pin "1") (pinfunction "G_1") (pintype "bidirectional"))
      (node (ref "R19") (pin "2") (pinfunction "2_2") (pintype "passive"))
      (node (ref "R22") (pin "2") (pinfunction "2_2") (pintype "passive"))
    )
    (net (code "59") (name "Net-(Q9-G)") (class "Default")
      (node (ref "Q9") (pin "1") (pinfunction "G_1") (pintype "bidirectional"))
      (node (ref "R20") (pin "2") (pinfunction "2_2") (pintype "passive"))
      (node (ref "R23") (pin "2") (pinfunction "2_2") (pintype "passive"))
    )
    (net (code "60") (name "Net-(Q10-D)") (class "Default")
      (node (ref "Q10") (pin "3") (pinfunction "D_3") (pintype "bidirectional"))
      (node (ref "Q13") (pin "1") (pinfunction "G_1") (pintype "passive"))
      (node (ref "R27") (pin "1") (pinfunction "1_1") (pintype "passive"))
    )
    (net (code "61") (name "Net-(Q10-G)") (class "Default")
      (node (ref "Q10") (pin "1") (pinfunction "G_1") (pintype "bidirectional"))
      (node (ref "R21") (pin "2") (pinfunction "2_2") (pintype "passive"))
      (node (ref "R24") (pin "2") (pinfunction "2_2") (pintype "passive"))
    )
    (net (code "62") (name "Net-(Q11-G)") (class "Default")
      (node (ref "Q11") (pin "1") (pinfunction "G_1") (pintype "passive"))
      (node (ref "Q8") (pin "3") (pinfunction "D_3") (pintype "bidirectional"))
      (node (ref "R25") (pin "1") (pinfunction "1_1") (pintype "passive"))
    )
    (net (code "63") (name "Net-(Q12-G)") (class "Default")
      (node (ref "Q12") (pin "1") (pinfunction "G_1") (pintype "passive"))
      (node (ref "Q9") (pin "3") (pinfunction "D_3") (pintype "bidirectional"))
      (node (ref "R26") (pin "1") (pinfunction "1_1") (pintype "passive"))
    )
    (net (code "64") (name "Net-(Q14-D)") (class "Default")
      (node (ref "Q14") (pin "3") (pinfunction "D_3") (pintype "bidirectional"))
      (node (ref "Q17") (pin "1") (pinfunction "G_1") (pintype "passive"))
      (node (ref "R37") (pin "1") (pinfunction "1_1") (pintype "passive"))
    )
    (net (code "65") (name "Net-(Q14-G)") (class "Default")
      (node (ref "Q14") (pin "1") (pinfunction "G_1") (pintype "bidirectional"))
      (node (ref "R31") (pin "2") (pinfunction "2_2") (pintype "passive"))
      (node (ref "R34") (pin "2") (pinfunction "2_2") (pintype "passive"))
    )
    (net (code "66") (name "Net-(Q15-D)") (class "Default")
      (node (ref "Q15") (pin "3") (pinfunction "D_3") (pintype "bidirectional"))
      (node (ref "Q18") (pin "1") (pinfunction "G_1") (pintype "passive"))
      (node (ref "R38") (pin "1") (pinfunction "1_1") (pintype "passive"))
    )
    (net (code "67") (name "Net-(Q15-G)") (class "Default")
      (node (ref "Q15") (pin "1") (pinfunction "G_1") (pintype "bidirectional"))
      (node (ref "R32") (pin "2") (pinfunction "2_2") (pintype "passive"))
      (node (ref "R35") (pin "2") (pinfunction "2_2") (pintype "passive"))
    )
    (net (code "68") (name "Net-(Q16-D)") (class "Default")
      (node (ref "Q16") (pin "3") (pinfunction "D_3") (pintype "bidirectional"))
      (node (ref "Q19") (pin "1") (pinfunction "G_1") (pintype "passive"))
      (node (ref "R39") (pin "1") (pinfunction "1_1") (pintype "passive"))
    )
    (net (code "69") (name "Net-(Q16-G)") (class "Default")
      (node (ref "Q16") (pin "1") (pinfunction "G_1") (pintype "bidirectional"))
      (node (ref "R33") (pin "2") (pinfunction "2_2") (pintype "passive"))
      (node (ref "R36") (pin "2") (pinfunction "2_2") (pintype "passive"))
    )
    (net (code "70") (name "Net-(Q20-G)") (class "Default")
      (node (ref "Q20") (pin "1") (pinfunction "G_1") (pintype "bidirectional"))
      (node (ref "R43") (pin "2") (pinfunction "2_2") (pintype "passive"))
      (node (ref "R48") (pin "2") (pinfunction "2_2") (pintype "passive"))
    )
    (net (code "71") (name "Net-(Q21-G)") (class "Default")
      (node (ref "Q21") (pin "1") (pinfunction "G_1") (pintype "bidirectional"))
      (node (ref "R44") (pin "2") (pinfunction "2_2") (pintype "passive"))
      (node (ref "R49") (pin "2") (pinfunction "2_2") (pintype "passive"))
    )
    (net (code "72") (name "Net-(Q22-G)") (class "Default")
      (node (ref "Q22") (pin "1") (pinfunction "G_1") (pintype "bidirectional"))
      (node (ref "R45") (pin "2") (pinfunction "2_2") (pintype "passive"))
      (node (ref "R50") (pin "2") (pinfunction "2_2") (pintype "passive"))
    )
    (net (code "73") (name "Net-(Q23-G)") (class "Default")
      (node (ref "Q23") (pin "1") (pinfunction "G_1") (pintype "bidirectional"))
      (node (ref "R46") (pin "2") (pinfunction "2_2") (pintype "passive"))
      (node (ref "R51") (pin "2") (pinfunction "2_2") (pintype "passive"))
    )
    (net (code "74") (name "Net-(Q24-G)") (class "Default")
      (node (ref "Q24") (pin "1") (pinfunction "G_1") (pintype "bidirectional"))
      (node (ref "R47") (pin "2") (pinfunction "2_2") (pintype "passive"))
      (node (ref "R52") (pin "2") (pinfunction "2_2") (pintype "passive"))
    )
    (net (code "75") (name "Net-(Q25-G)") (class "Default")
      (node (ref "Q25") (pin "1") (pinfunction "G_1") (pintype "bidirectional"))
      (node (ref "R53") (pin "2") (pinfunction "2_2") (pintype "passive"))
      (node (ref "R55") (pin "2") (pinfunction "2_2") (pintype "passive"))
    )
    (net (code "76") (name "Net-(Q26-G)") (class "Default")
      (node (ref "Q26") (pin "1") (pinfunction "G_1") (pintype "bidirectional"))
      (node (ref "R54") (pin "2") (pinfunction "2_2") (pintype "passive"))
      (node (ref "R56") (pin "2") (pinfunction "2_2") (pintype "passive"))
    )
    (net (code "77") (name "Net-(U$1-+5)") (class "Default")
      (node (ref "JP5") (pin "1") (pinfunction "1_1") (pintype "passive"))
      (node (ref "SJ1") (pin "1") (pinfunction "1_1") (pintype "passive"))
      (node (ref "U$1") (pin "P$1") (pinfunction "+5_P$1") (pintype "bidirectional"))
    )
    (net (code "78") (name "Net-(U$1-ID)") (class "Default")
      (node (ref "JP5") (pin "4") (pinfunction "4_4") (pintype "passive"))
      (node (ref "U$1") (pin "P$4") (pinfunction "ID_P$4") (pintype "bidirectional"))
    )
    (net (code "79") (name "Net-(U1-PB6{slash}XTAL1)") (class "Default")
      (node (ref "C2") (pin "2") (pinfunction "2_2") (pintype "passive"))
      (node (ref "Q1") (pin "1") (pinfunction "1_1") (pintype "passive"))
      (node (ref "U1") (pin "7") (pinfunction "PB6/XTAL1_7") (pintype "bidirectional"))
    )
    (net (code "80") (name "Net-(U1-PB7{slash}XTAL2)") (class "Default")
      (node (ref "C3") (pin "2") (pinfunction "2_2") (pintype "passive"))
      (node (ref "Q1") (pin "2") (pinfunction "2_2") (pintype "passive"))
      (node (ref "U1") (pin "8") (pinfunction "PB7/XTAL2_8") (pintype "bidirectional"))
    )
    (net (code "81") (name "Net-(U2-BYPASS)") (class "Default")
      (node (ref "C11") (pin "1") (pinfunction "1_1") (pintype "passive"))
      (node (ref "U2") (pin "1") (pinfunction "BYPASS_1") (pintype "bidirectional"))
    )
    (net (code "82") (name "Net-(U2-OUT)") (class "Default")
      (node (ref "C12") (pin "+") (pinfunction "+_+") (pintype "passive"))
      (node (ref "U2") (pin "8") (pinfunction "OUT_8") (pintype "bidirectional"))
    )
    (net (code "83") (name "Net-(U3-IN+)") (class "Default")
      (node (ref "C8") (pin "2") (pinfunction "2_2") (pintype "passive"))
      (node (ref "U3") (pin "3") (pinfunction "IN+_3") (pintype "bidirectional"))
    )
    (net (code "84") (name "Net-(U3-IN-)") (class "Default")
      (node (ref "C9") (pin "2") (pinfunction "2_2") (pintype "passive"))
      (node (ref "U3") (pin "4") (pinfunction "IN-_4") (pintype "bidirectional"))
    )
    (net (code "85") (name "Net-(U4-B)") (class "Default")
      (node (ref "R57") (pin "2") (pinfunction "2_2") (pintype "passive"))
      (node (ref "U4") (pin "4") (pinfunction "B_4") (pintype "bidirectional"))
    )
    (net (code "86") (name "Net-(X15B-KL)") (class "Default")
      (node (ref "X15") (pin "2") (pinfunction "KL_2") (pintype "passive"))
      (node (ref "X16") (pin "1") (pinfunction "KL_1") (pintype "passive"))
    )
    (net (code "87") (name "RX") (class "Default")
      (node (ref "JP1") (pin "3") (pinfunction "3_3") (pintype "passive"))
      (node (ref "JP2") (pin "1") (pinfunction "1_1") (pintype "passive"))
      (node (ref "U1") (pin "30") (pinfunction "PD0_30") (pintype "bidirectional"))
    )
    (net (code "88") (name "SCK") (class "Default")
      (node (ref "IC1") (pin "11") (pinfunction "SCK_11") (pintype "input"))
      (node (ref "IC2") (pin "11") (pinfunction "SCK_11") (pintype "input"))
      (node (ref "ISP1") (pin "3") (pinfunction "SCK_3") (pintype "output"))
      (node (ref "U1") (pin "17") (pinfunction "PB5_17") (pintype "bidirectional"))
      (node (ref "U4") (pin "11") (pinfunction "SCLK_SCL_11") (pintype "bidirectional"))
      (node (ref "X3") (pin "3") (pinfunction "S_3") (pintype "passive"))
    )
    (net (code "89") (name "SCORE0_1") (class "Default")
      (node (ref "Q5") (pin "3") (pinfunction "D_3") (pintype "passive"))
      (node (ref "R16") (pin "2") (pinfunction "2_2") (pintype "passive"))
      (node (ref "X6") (pin "8") (pinfunction "S_8") (pintype "passive"))
    )
    (net (code "90") (name "SCORE0_10") (class "Default")
      (node (ref "Q11") (pin "3") (pinfunction "D_3") (pintype "passive"))
      (node (ref "R28") (pin "2") (pinfunction "2_2") (pintype "passive"))
      (node (ref "X7") (pin "8") (pinfunction "S_8") (pintype "passive"))
    )
    (net (code "91") (name "SCORE0_100") (class "Default")
      (node (ref "Q17") (pin "3") (pinfunction "D_3") (pintype "passive"))
      (node (ref "R40") (pin "2") (pinfunction "2_2") (pintype "passive"))
      (node (ref "X8") (pin "8") (pinfunction "S_8") (pintype "passive"))
    )
    (net (code "92") (name "SCORE1_1") (class "Default")
      (node (ref "Q6") (pin "3") (pinfunction "D_3") (pintype "passive"))
      (node (ref "R17") (pin "2") (pinfunction "2_2") (pintype "passive"))
      (node (ref "X9") (pin "8") (pinfunction "S_8") (pintype "passive"))
    )
    (net (code "93") (name "SCORE1_10") (class "Default")
      (node (ref "Q12") (pin "3") (pinfunction "D_3") (pintype "passive"))
      (node (ref "R29") (pin "2") (pinfunction "2_2") (pintype "passive"))
      (node (ref "X10") (pin "8") (pinfunction "S_8") (pintype "passive"))
    )
    (net (code "94") (name "SCORE1_100") (class "Default")
      (node (ref "Q18") (pin "3") (pinfunction "D_3") (pintype "passive"))
      (node (ref "R41") (pin "2") (pinfunction "2_2") (pintype "passive"))
      (node (ref "X11") (pin "8") (pinfunction "S_8") (pintype "passive"))
    )
    (net (code "95") (name "SCORE2_1") (class "Default")
      (node (ref "Q7") (pin "3") (pinfunction "D_3") (pintype "passive"))
      (node (ref "R18") (pin "2") (pinfunction "2_2") (pintype "passive"))
      (node (ref "X12") (pin "8") (pinfunction "S_8") (pintype "passive"))
    )
    (net (code "96") (name "SCORE2_10") (class "Default")
      (node (ref "Q13") (pin "3") (pinfunction "D_3") (pintype "passive"))
      (node (ref "R30") (pin "2") (pinfunction "2_2") (pintype "passive"))
      (node (ref "X13") (pin "8") (pinfunction "S_8") (pintype "passive"))
    )
    (net (code "97") (name "SCORE2_100") (class "Default")
      (node (ref "Q19") (pin "3") (pinfunction "D_3") (pintype "passive"))
      (node (ref "R42") (pin "2") (pinfunction "2_2") (pintype "passive"))
      (node (ref "X14") (pin "8") (pinfunction "S_8") (pintype "passive"))
    )
    (net (code "98") (name "SIGA") (class "Default")
      (node (ref "IC1") (pin "15") (pinfunction "QA_15") (pintype "tri_state"))
      (node (ref "R43") (pin "1") (pinfunction "1_1") (pintype "passive"))
    )
    (net (code "99") (name "SIGB") (class "Default")
      (node (ref "IC1") (pin "1") (pinfunction "QB_1") (pintype "tri_state"))
      (node (ref "R44") (pin "1") (pinfunction "1_1") (pintype "passive"))
    )
    (net (code "100") (name "SIGC") (class "Default")
      (node (ref "IC1") (pin "2") (pinfunction "QC_2") (pintype "tri_state"))
      (node (ref "R45") (pin "1") (pinfunction "1_1") (pintype "passive"))
    )
    (net (code "101") (name "SIGD") (class "Default")
      (node (ref "IC1") (pin "3") (pinfunction "QD_3") (pintype "tri_state"))
      (node (ref "R46") (pin "1") (pinfunction "1_1") (pintype "passive"))
    )
    (net (code "102") (name "SIGE") (class "Default")
      (node (ref "IC1") (pin "4") (pinfunction "QE_4") (pintype "tri_state"))
      (node (ref "R47") (pin "1") (pinfunction "1_1") (pintype "passive"))
    )
    (net (code "103") (name "SIGF") (class "Default")
      (node (ref "IC1") (pin "5") (pinfunction "QF_5") (pintype "tri_state"))
      (node (ref "R53") (pin "1") (pinfunction "1_1") (pintype "passive"))
    )
    (net (code "104") (name "SIGG") (class "Default")
      (node (ref "IC1") (pin "6") (pinfunction "QG_6") (pintype "tri_state"))
      (node (ref "R54") (pin "1") (pinfunction "1_1") (pintype "passive"))
    )
    (net (code "105") (name "SOUND+") (class "Default")
      (node (ref "SJ4") (pin "2") (pinfunction "2_2") (pintype "passive"))
      (node (ref "X15") (pin "1") (pinfunction "KL_1") (pintype "passive"))
    )
    (net (code "106") (name "SOUND-") (class "Default")
      (node (ref "SJ5") (pin "2") (pinfunction "2_2") (pintype "passive"))
      (node (ref "X16") (pin "2") (pinfunction "KL_2") (pintype "passive"))
    )
    (net (code "107") (name "SOUNDOUT") (class "Default")
      (node (ref "SJ6") (pin "2") (pinfunction "2_2") (pintype "passive"))
      (node (ref "U1") (pin "13") (pinfunction "PB1_13") (pintype "bidirectional"))
      (node (ref "U4") (pin "2") (pinfunction "A_2") (pintype "bidirectional"))
    )
    (net (code "108") (name "SOUND_ATND") (class "Default")
      (node (ref "C8") (pin "1") (pinfunction "1_1") (pintype "passive"))
      (node (ref "SJ6") (pin "1") (pinfunction "1_1") (pintype "passive"))
      (node (ref "U2") (pin "2") (pinfunction "IN+_2") (pintype "bidirectional"))
      (node (ref "U4") (pin "3") (pinfunction "W_3") (pintype "bidirectional"))
    )
    (net (code "109") (name "SOUND_CS") (class "Default")
      (node (ref "R4") (pin "1") (pinfunction "1_1") (pintype "passive"))
      (node (ref "U1") (pin "14") (pinfunction "PB2_14") (pintype "bidirectional"))
      (node (ref "U4") (pin "6") (pinfunction "SY_AD0_6") (pintype "bidirectional"))
    )
    (net (code "110") (name "TX") (class "Default")
      (node (ref "JP1") (pin "1") (pinfunction "1_1") (pintype "passive"))
      (node (ref "JP2") (pin "3") (pinfunction "3_3") (pintype "passive"))
      (node (ref "U1") (pin "31") (pinfunction "PD1_31") (pintype "bidirectional"))
    )
    (net (code "111") (name "UCD+") (class "Default")
      (node (ref "R60") (pin "1") (pinfunction "1_1") (pintype "passive"))
      (node (ref "U1") (pin "6") (pinfunction "PE1_6") (pintype "bidirectional"))
    )
    (net (code "112") (name "UCD-") (class "Default")
      (node (ref "R63") (pin "2") (pinfunction "2_2") (pintype "passive"))
      (node (ref "U1") (pin "3") (pinfunction "PE0_3") (pintype "bidirectional"))
    )
    (net (code "113") (name "UC_RESET") (class "Default")
      (node (ref "C1") (pin "1") (pinfunction "1_1") (pintype "passive"))
      (node (ref "C5") (pin "2") (pinfunction "2_2") (pintype "passive"))
      (node (ref "ISP1") (pin "5") (pinfunction "RST_5") (pintype "output"))
      (node (ref "R6") (pin "1") (pinfunction "1_1") (pintype "passive"))
      (node (ref "RESET") (pin "3") (pinfunction "B1_3") (pintype "bidirectional"))
      (node (ref "U1") (pin "29") (pinfunction "PC6/RESET_29") (pintype "bidirectional"))
    )
    (net (code "114") (name "unconnected-(RESET-A2-Pad2)") (class "Default")
      (node (ref "RESET") (pin "2") (pinfunction "A2_2") (pintype "bidirectional"))
    )
    (net (code "115") (name "unconnected-(RESET-B2-Pad4)") (class "Default")
      (node (ref "RESET") (pin "4") (pinfunction "B2_4") (pintype "bidirectional"))
    )
  )
)
